# PlayerBottom.net
KiCad netlist of a schematic drawn in EAGLE
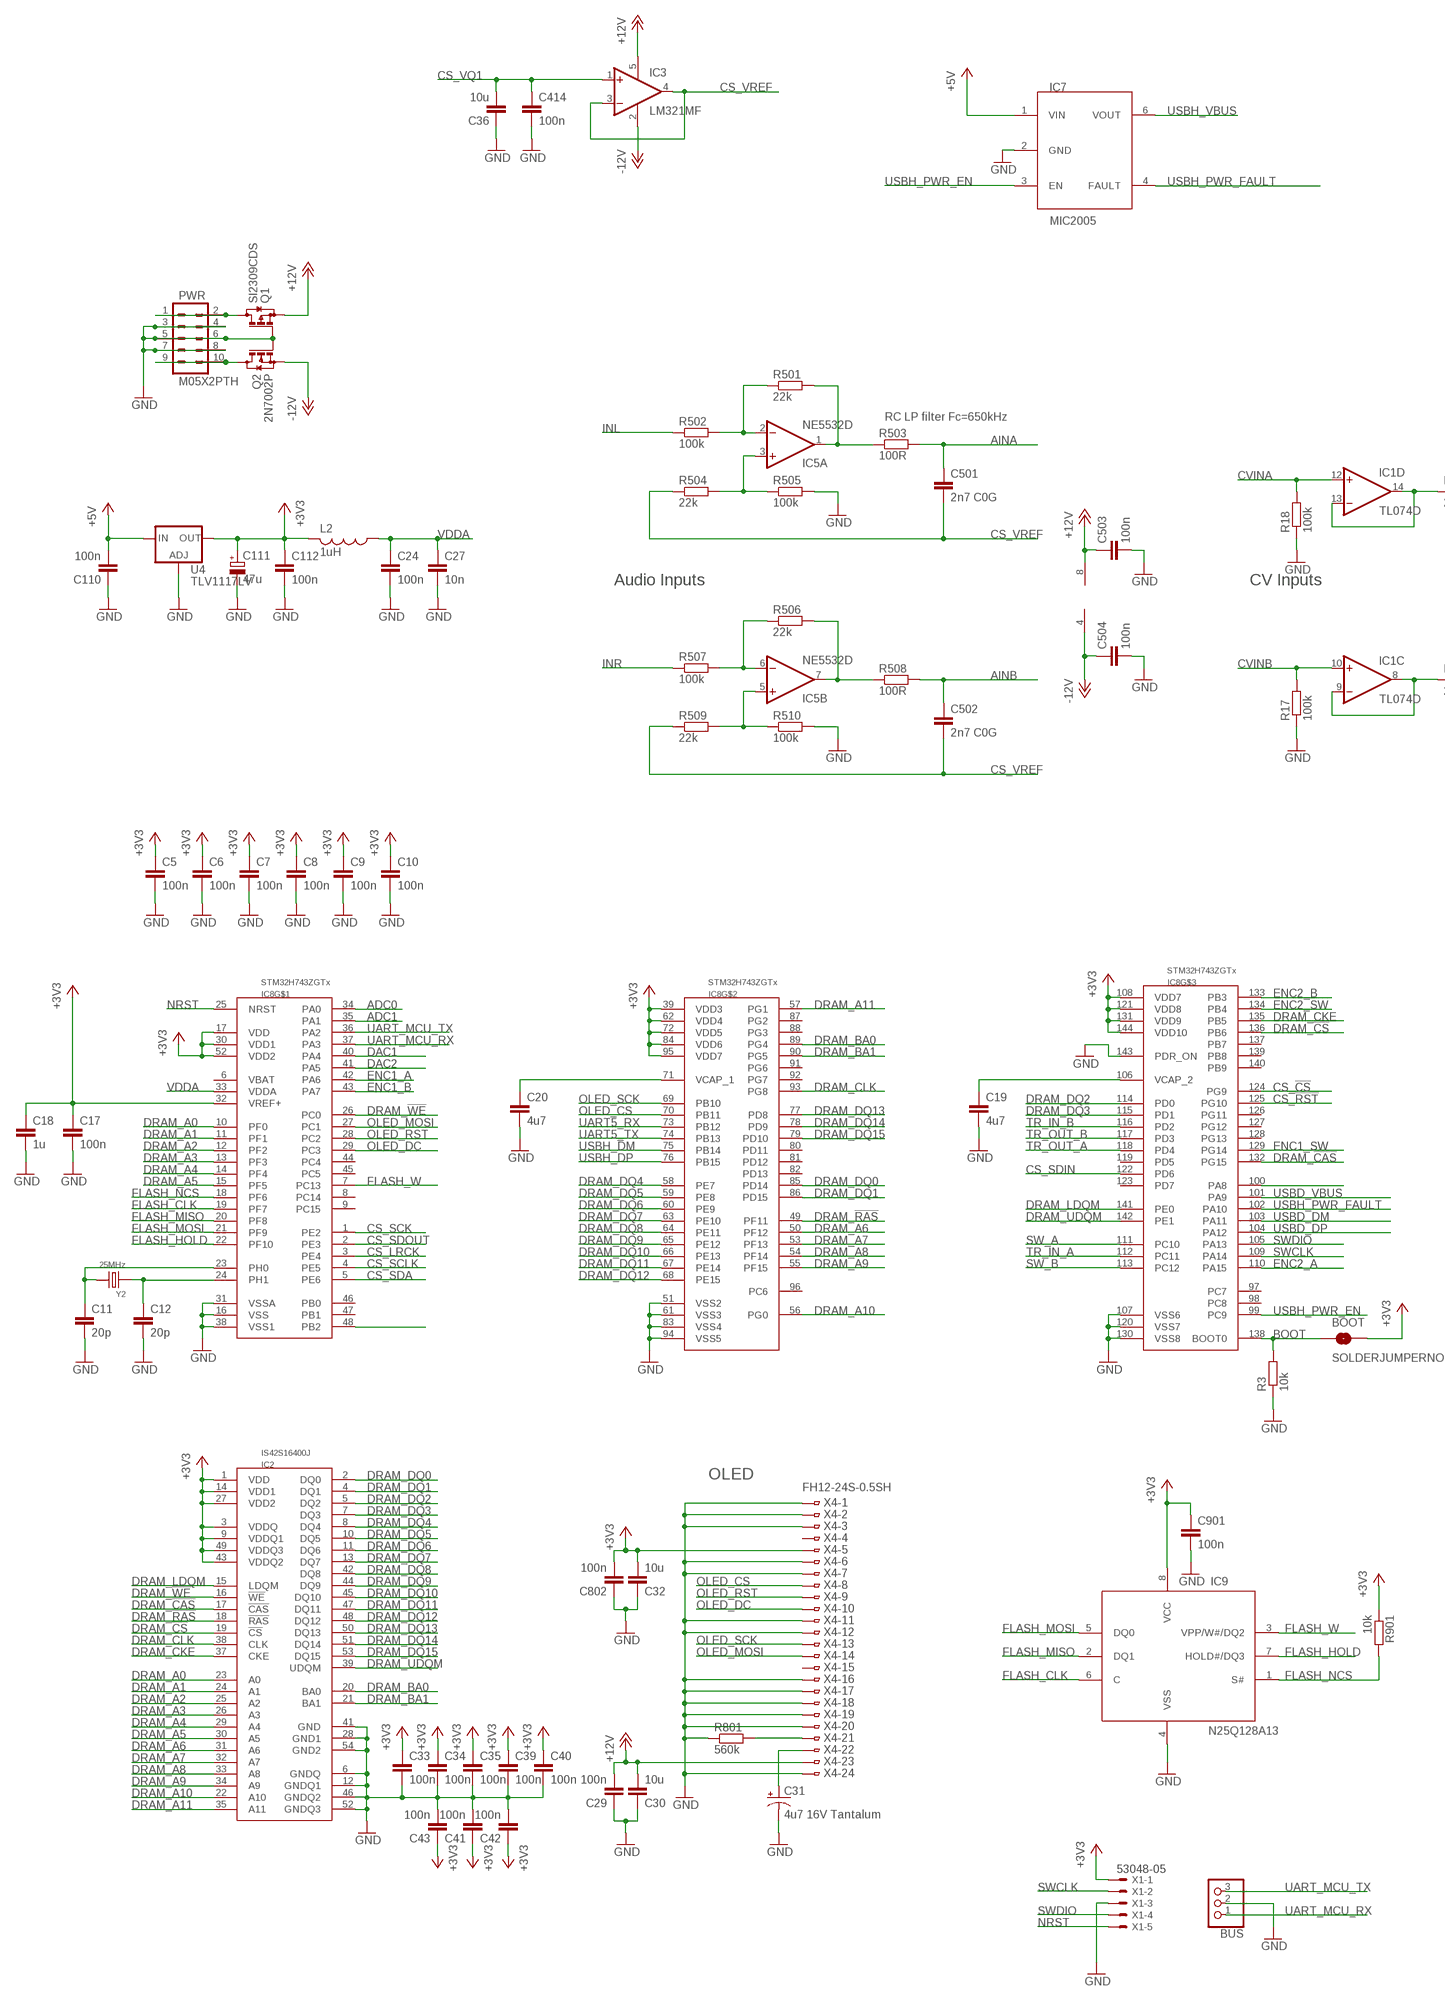
[diagram p0: schematic, sheet 1, part 1 of 2]
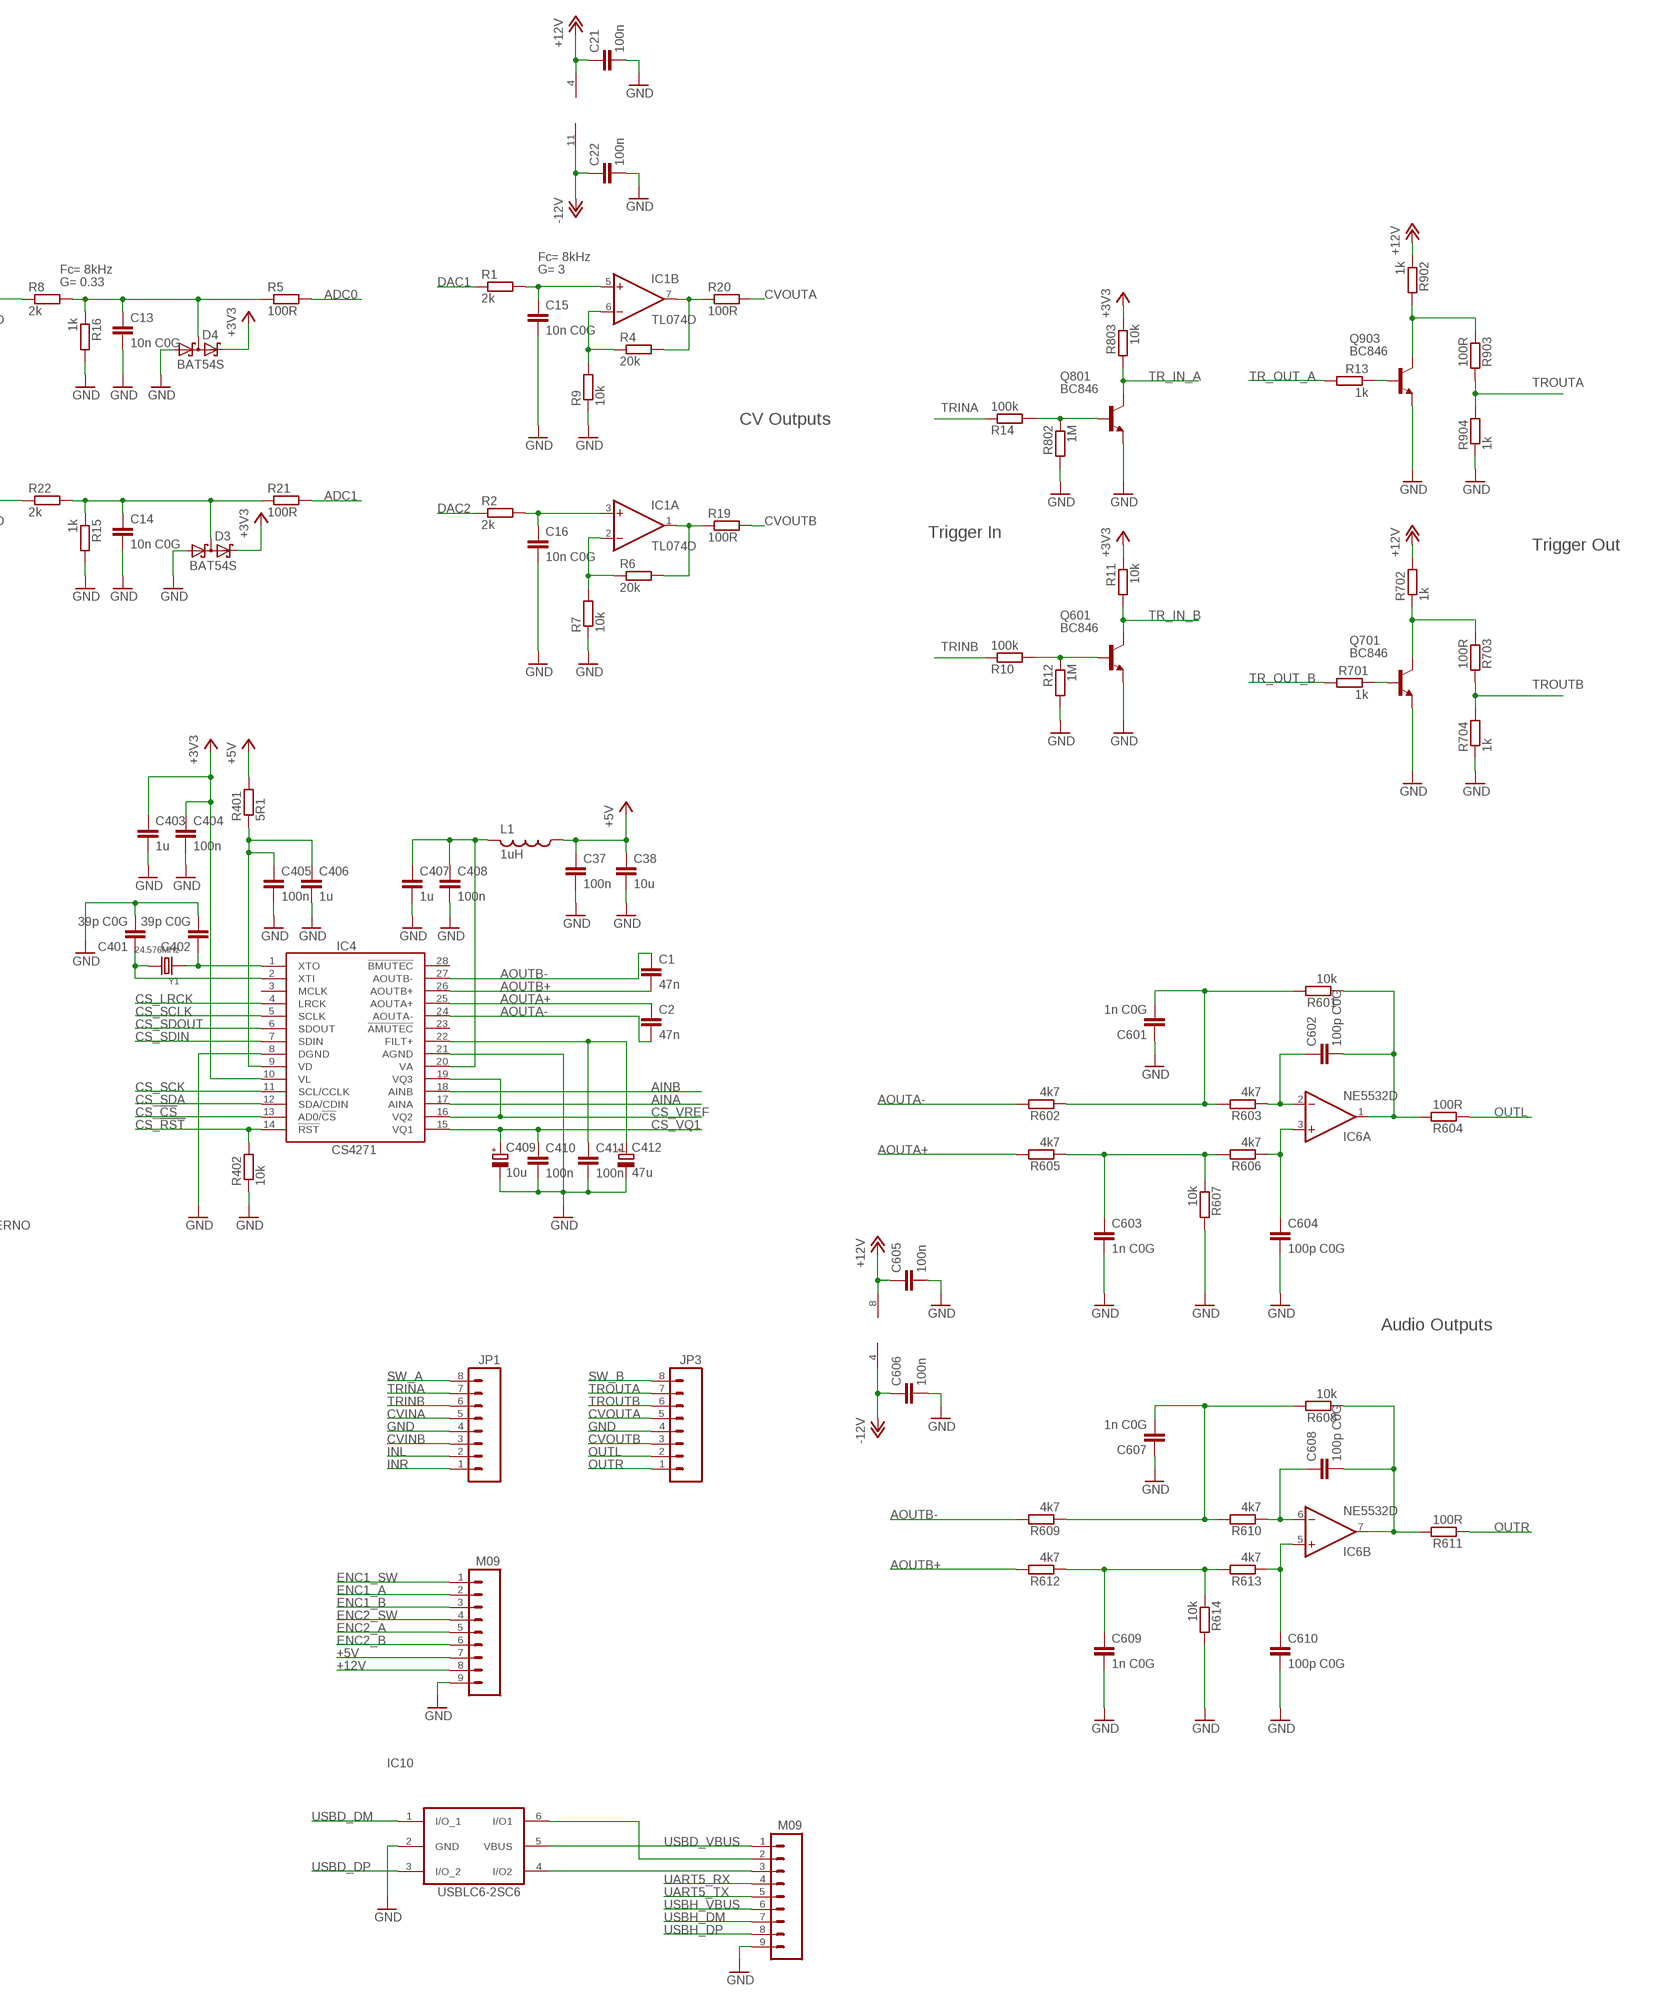
[diagram p1: schematic, sheet 1, part 2 of 2]

(export (version "E")
  (design (tool "Eeschema 10.0.6"))
  (components
    (comp (ref "BOOT")
      (value "SOLDERJUMPERNO")
      (footprint "eagle-import:SJ_2S-NO")
      (libsource (lib "eagle-import") (part "SOLDERJUMPERNO"))
    )
    (comp (ref "BUS")
      (value "CON-JST-1X03PH-TH")
      (footprint "eagle-import:JST-B3B-PH-KL")
      (libsource (lib "eagle-import") (part "CON-JST-1X03PH-TH"))
    )
    (comp (ref "C1")
      (value "47n")
      (footprint "eagle-import:C0603")
      (libsource (lib "eagle-import") (part "C-EUC0603"))
    )
    (comp (ref "C2")
      (value "47n")
      (footprint "eagle-import:C0603")
      (libsource (lib "eagle-import") (part "C-EUC0603"))
    )
    (comp (ref "C5")
      (value "100n")
      (footprint "eagle-import:C0603")
      (libsource (lib "eagle-import") (part "C-EUC0603"))
    )
    (comp (ref "C6")
      (value "100n")
      (footprint "eagle-import:C0603")
      (libsource (lib "eagle-import") (part "C-EUC0603"))
    )
    (comp (ref "C7")
      (value "100n")
      (footprint "eagle-import:C0603")
      (libsource (lib "eagle-import") (part "C-EUC0603"))
    )
    (comp (ref "C8")
      (value "100n")
      (footprint "eagle-import:C0603")
      (libsource (lib "eagle-import") (part "C-EUC0603"))
    )
    (comp (ref "C9")
      (value "100n")
      (footprint "eagle-import:C0603")
      (libsource (lib "eagle-import") (part "C-EUC0603"))
    )
    (comp (ref "C10")
      (value "100n")
      (footprint "eagle-import:C0603")
      (libsource (lib "eagle-import") (part "C-EUC0603"))
    )
    (comp (ref "C11")
      (value "20p")
      (footprint "eagle-import:C0603")
      (libsource (lib "eagle-import") (part "C-EUC0603"))
    )
    (comp (ref "C12")
      (value "20p")
      (footprint "eagle-import:C0603")
      (libsource (lib "eagle-import") (part "C-EUC0603"))
    )
    (comp (ref "C13")
      (value "10n C0G")
      (footprint "eagle-import:C0603")
      (libsource (lib "eagle-import") (part "C-EUC0603"))
    )
    (comp (ref "C14")
      (value "10n C0G")
      (footprint "eagle-import:C0603")
      (libsource (lib "eagle-import") (part "C-EUC0603"))
    )
    (comp (ref "C15")
      (value "10n C0G")
      (footprint "eagle-import:C0603")
      (libsource (lib "eagle-import") (part "C-EUC0603"))
    )
    (comp (ref "C16")
      (value "10n C0G")
      (footprint "eagle-import:C0603")
      (libsource (lib "eagle-import") (part "C-EUC0603"))
    )
    (comp (ref "C17")
      (value "100n")
      (footprint "eagle-import:C0603")
      (libsource (lib "eagle-import") (part "C-EUC0603"))
    )
    (comp (ref "C18")
      (value "1u")
      (footprint "eagle-import:C0603")
      (libsource (lib "eagle-import") (part "C-EUC0603"))
    )
    (comp (ref "C19")
      (value "4u7")
      (footprint "eagle-import:C0603")
      (libsource (lib "eagle-import") (part "C-EUC0603"))
    )
    (comp (ref "C20")
      (value "4u7")
      (footprint "eagle-import:C0603")
      (libsource (lib "eagle-import") (part "C-EUC0603"))
    )
    (comp (ref "C21")
      (value "100n")
      (footprint "eagle-import:C0603")
      (libsource (lib "eagle-import") (part "C-EUC0603"))
    )
    (comp (ref "C22")
      (value "100n")
      (footprint "eagle-import:C0603")
      (libsource (lib "eagle-import") (part "C-EUC0603"))
    )
    (comp (ref "C24")
      (value "100n")
      (footprint "eagle-import:C0603")
      (libsource (lib "eagle-import") (part "C-EUC0603"))
    )
    (comp (ref "C27")
      (value "10n")
      (footprint "eagle-import:C0603")
      (libsource (lib "eagle-import") (part "C-EUC0603"))
    )
    (comp (ref "C29")
      (value "100n")
      (footprint "eagle-import:C0603")
      (libsource (lib "eagle-import") (part "C-EUC0603"))
    )
    (comp (ref "C30")
      (value "10u")
      (footprint "eagle-import:C1206")
      (libsource (lib "eagle-import") (part "C-EUC1206"))
    )
    (comp (ref "C31")
      (value "4u7 16V Tantalum")
      (footprint "eagle-import:EIA3216")
      (libsource (lib "eagle-import") (part "CAP_POL1206"))
    )
    (comp (ref "C32")
      (value "10u")
      (footprint "eagle-import:C1206")
      (libsource (lib "eagle-import") (part "C-EUC1206"))
    )
    (comp (ref "C33")
      (value "100n")
      (footprint "eagle-import:C0603")
      (libsource (lib "eagle-import") (part "C-EUC0603"))
    )
    (comp (ref "C34")
      (value "100n")
      (footprint "eagle-import:C0603")
      (libsource (lib "eagle-import") (part "C-EUC0603"))
    )
    (comp (ref "C35")
      (value "100n")
      (footprint "eagle-import:C0603")
      (libsource (lib "eagle-import") (part "C-EUC0603"))
    )
    (comp (ref "C36")
      (value "10u")
      (footprint "eagle-import:C1206")
      (libsource (lib "eagle-import") (part "C-EUC1206"))
    )
    (comp (ref "C37")
      (value "100n")
      (footprint "eagle-import:C0603")
      (libsource (lib "eagle-import") (part "C-EUC0603"))
    )
    (comp (ref "C38")
      (value "10u")
      (footprint "eagle-import:C1206")
      (libsource (lib "eagle-import") (part "C-EUC1206"))
    )
    (comp (ref "C39")
      (value "100n")
      (footprint "eagle-import:C0603")
      (libsource (lib "eagle-import") (part "C-EUC0603"))
    )
    (comp (ref "C40")
      (value "100n")
      (footprint "eagle-import:C0603")
      (libsource (lib "eagle-import") (part "C-EUC0603"))
    )
    (comp (ref "C41")
      (value "100n")
      (footprint "eagle-import:C0603")
      (libsource (lib "eagle-import") (part "C-EUC0603"))
    )
    (comp (ref "C42")
      (value "100n")
      (footprint "eagle-import:C0603")
      (libsource (lib "eagle-import") (part "C-EUC0603"))
    )
    (comp (ref "C43")
      (value "100n")
      (footprint "eagle-import:C0603")
      (libsource (lib "eagle-import") (part "C-EUC0603"))
    )
    (comp (ref "C110")
      (value "100n")
      (footprint "eagle-import:C0603")
      (libsource (lib "eagle-import") (part "C-EUC0603"))
    )
    (comp (ref "C111")
      (value "47u")
      (footprint "eagle-import:CPOL-5")
      (libsource (lib "eagle-import") (part "CPOL-EU153CLV-0505"))
    )
    (comp (ref "C112")
      (value "100n")
      (footprint "eagle-import:C0603")
      (libsource (lib "eagle-import") (part "C-EUC0603"))
    )
    (comp (ref "C401")
      (value "39p C0G")
      (footprint "eagle-import:C0603")
      (libsource (lib "eagle-import") (part "C-EUC0603"))
    )
    (comp (ref "C402")
      (value "39p C0G")
      (footprint "eagle-import:C0603")
      (libsource (lib "eagle-import") (part "C-EUC0603"))
    )
    (comp (ref "C403")
      (value "1u")
      (footprint "eagle-import:C0603")
      (libsource (lib "eagle-import") (part "C-EUC0603"))
    )
    (comp (ref "C404")
      (value "100n")
      (footprint "eagle-import:C0603")
      (libsource (lib "eagle-import") (part "C-EUC0603"))
    )
    (comp (ref "C405")
      (value "100n")
      (footprint "eagle-import:C0603")
      (libsource (lib "eagle-import") (part "C-EUC0603"))
    )
    (comp (ref "C406")
      (value "1u")
      (footprint "eagle-import:C0603")
      (libsource (lib "eagle-import") (part "C-EUC0603"))
    )
    (comp (ref "C407")
      (value "1u")
      (footprint "eagle-import:C0603")
      (libsource (lib "eagle-import") (part "C-EUC0603"))
    )
    (comp (ref "C408")
      (value "100n")
      (footprint "eagle-import:C0603")
      (libsource (lib "eagle-import") (part "C-EUC0603"))
    )
    (comp (ref "C409")
      (value "10u")
      (footprint "eagle-import:CPOL-5")
      (libsource (lib "eagle-import") (part "CPOL-EU153CLV-0505"))
    )
    (comp (ref "C410")
      (value "100n")
      (footprint "eagle-import:C0603")
      (libsource (lib "eagle-import") (part "C-EUC0603"))
    )
    (comp (ref "C411")
      (value "100n")
      (footprint "eagle-import:C0603")
      (libsource (lib "eagle-import") (part "C-EUC0603"))
    )
    (comp (ref "C412")
      (value "47u")
      (footprint "eagle-import:CPOL-5")
      (libsource (lib "eagle-import") (part "CPOL-EU153CLV-0505"))
    )
    (comp (ref "C414")
      (value "100n")
      (footprint "eagle-import:C0603")
      (libsource (lib "eagle-import") (part "C-EUC0603"))
    )
    (comp (ref "C501")
      (value "2n7 C0G")
      (footprint "eagle-import:C0603")
      (libsource (lib "eagle-import") (part "C-EUC0603"))
    )
    (comp (ref "C502")
      (value "2n7 C0G")
      (footprint "eagle-import:C0603")
      (libsource (lib "eagle-import") (part "C-EUC0603"))
    )
    (comp (ref "C503")
      (value "100n")
      (footprint "eagle-import:C0603")
      (libsource (lib "eagle-import") (part "C-EUC0603"))
    )
    (comp (ref "C504")
      (value "100n")
      (footprint "eagle-import:C0603")
      (libsource (lib "eagle-import") (part "C-EUC0603"))
    )
    (comp (ref "C601")
      (value "1n C0G")
      (footprint "eagle-import:C0603")
      (libsource (lib "eagle-import") (part "C-EUC0603"))
    )
    (comp (ref "C602")
      (value "100p C0G")
      (footprint "eagle-import:C0603")
      (libsource (lib "eagle-import") (part "C-EUC0603"))
    )
    (comp (ref "C603")
      (value "1n C0G")
      (footprint "eagle-import:C0603")
      (libsource (lib "eagle-import") (part "C-EUC0603"))
    )
    (comp (ref "C604")
      (value "100p C0G")
      (footprint "eagle-import:C0603")
      (libsource (lib "eagle-import") (part "C-EUC0603"))
    )
    (comp (ref "C605")
      (value "100n")
      (footprint "eagle-import:C0603")
      (libsource (lib "eagle-import") (part "C-EUC0603"))
    )
    (comp (ref "C606")
      (value "100n")
      (footprint "eagle-import:C0603")
      (libsource (lib "eagle-import") (part "C-EUC0603"))
    )
    (comp (ref "C607")
      (value "1n C0G")
      (footprint "eagle-import:C0603")
      (libsource (lib "eagle-import") (part "C-EUC0603"))
    )
    (comp (ref "C608")
      (value "100p C0G")
      (footprint "eagle-import:C0603")
      (libsource (lib "eagle-import") (part "C-EUC0603"))
    )
    (comp (ref "C609")
      (value "1n C0G")
      (footprint "eagle-import:C0603")
      (libsource (lib "eagle-import") (part "C-EUC0603"))
    )
    (comp (ref "C610")
      (value "100p C0G")
      (footprint "eagle-import:C0603")
      (libsource (lib "eagle-import") (part "C-EUC0603"))
    )
    (comp (ref "C802")
      (value "100n")
      (footprint "eagle-import:C0603")
      (libsource (lib "eagle-import") (part "C-EUC0603"))
    )
    (comp (ref "C901")
      (value "100n")
      (footprint "eagle-import:C0603")
      (libsource (lib "eagle-import") (part "C-EUC0603"))
    )
    (comp (ref "D3")
      (value "BAT54S")
      (footprint "eagle-import:SOT23")
      (libsource (lib "eagle-import") (part "BAT54S"))
    )
    (comp (ref "D4")
      (value "BAT54S")
      (footprint "eagle-import:SOT23")
      (libsource (lib "eagle-import") (part "BAT54S"))
    )
    (comp (ref "IC1")
      (value "TL074D")
      (footprint "eagle-import:SO14")
      (libsource (lib "eagle-import") (part "TL074D"))
    )
    (comp (ref "IC2")
      (value "IS42S16400J")
      (footprint "eagle-import:TSOP54-400")
      (libsource (lib "eagle-import") (part "IS42S16400J"))
    )
    (comp (ref "IC3")
      (value "LM321MF")
      (footprint "eagle-import:SOT23-5")
      (libsource (lib "eagle-import") (part "LM321?MF"))
    )
    (comp (ref "IC4")
      (value "CS4271")
      (footprint "eagle-import:TSSOP28-0.65-9.7X4.4MM")
      (libsource (lib "eagle-import") (part "CS4271"))
    )
    (comp (ref "IC5")
      (value "NE5532D")
      (footprint "eagle-import:SO08")
      (libsource (lib "eagle-import") (part "NE5532D"))
    )
    (comp (ref "IC6")
      (value "NE5532D")
      (footprint "eagle-import:SO08")
      (libsource (lib "eagle-import") (part "NE5532D"))
    )
    (comp (ref "IC7")
      (value "MIC2005")
      (footprint "eagle-import:SOT23-6")
      (libsource (lib "eagle-import") (part "MIC2005"))
    )
    (comp (ref "IC8")
      (value "STM32H743ZGTx")
      (footprint "eagle-import:QFP50P2200X2200X160-144N")
      (fields (field (name "OC_FARNELL") "2484975"))
      (libsource (lib "eagle-import") (part "STM32F42XZ/43XZ(144PIN)LQFP144"))
    )
    (comp (ref "IC9")
      (value "N25Q128A13")
      (footprint "eagle-import:SO8W")
      (libsource (lib "eagle-import") (part "N25Q128A13"))
    )
    (comp (ref "IC10")
      (value "USBLC6-2SC6")
      (footprint "eagle-import:SOT-23-6L")
      (libsource (lib "eagle-import") (part "USBLC6-2SC6"))
    )
    (comp (ref "JP1")
      (value "M081X08")
      (footprint "eagle-import:1X08")
      (libsource (lib "eagle-import") (part "M081X08"))
    )
    (comp (ref "JP2")
      (value "M09")
      (footprint "eagle-import:1X09")
      (libsource (lib "eagle-import") (part "M09"))
    )
    (comp (ref "JP3")
      (value "M081X08")
      (footprint "eagle-import:1X08")
      (libsource (lib "eagle-import") (part "M081X08"))
    )
    (comp (ref "JP4")
      (value "M09")
      (footprint "eagle-import:1X09")
      (libsource (lib "eagle-import") (part "M09"))
    )
    (comp (ref "L1")
      (value "1uH")
      (footprint "eagle-import:0603")
      (libsource (lib "eagle-import") (part "INDUCTOR"))
    )
    (comp (ref "L2")
      (value "1uH")
      (footprint "eagle-import:0603")
      (libsource (lib "eagle-import") (part "INDUCTOR"))
    )
    (comp (ref "PWR")
      (value "M05X2PTH")
      (footprint "eagle-import:AVR_ICSP")
      (libsource (lib "eagle-import") (part "M05X2PTH"))
    )
    (comp (ref "Q1")
      (value "SI2309CDS")
      (footprint "eagle-import:SOT23")
      (libsource (lib "eagle-import") (part "BSS84"))
    )
    (comp (ref "Q2")
      (value "2N7002P")
      (footprint "eagle-import:SOT23")
      (libsource (lib "eagle-import") (part "BSS123"))
    )
    (comp (ref "Q601")
      (value "BC846")
      (footprint "eagle-import:SOT23")
      (libsource (lib "eagle-import") (part "BC846"))
    )
    (comp (ref "Q701")
      (value "BC846")
      (footprint "eagle-import:SOT23")
      (libsource (lib "eagle-import") (part "BC846"))
    )
    (comp (ref "Q801")
      (value "BC846")
      (footprint "eagle-import:SOT23")
      (libsource (lib "eagle-import") (part "BC846"))
    )
    (comp (ref "Q903")
      (value "BC846")
      (footprint "eagle-import:SOT23")
      (libsource (lib "eagle-import") (part "BC846"))
    )
    (comp (ref "R1")
      (value "2k")
      (footprint "eagle-import:0603")
      (libsource (lib "eagle-import") (part "R-EU_0603"))
    )
    (comp (ref "R2")
      (value "2k")
      (footprint "eagle-import:0603")
      (libsource (lib "eagle-import") (part "R-EU_0603"))
    )
    (comp (ref "R3")
      (value "10k")
      (footprint "eagle-import:0603")
      (libsource (lib "eagle-import") (part "R-EU_0603"))
    )
    (comp (ref "R4")
      (value "20k")
      (footprint "eagle-import:0603")
      (libsource (lib "eagle-import") (part "R-EU_0603"))
    )
    (comp (ref "R5")
      (value "100R")
      (footprint "eagle-import:0603")
      (libsource (lib "eagle-import") (part "R-EU_0603"))
    )
    (comp (ref "R6")
      (value "20k")
      (footprint "eagle-import:0603")
      (libsource (lib "eagle-import") (part "R-EU_0603"))
    )
    (comp (ref "R7")
      (value "10k")
      (footprint "eagle-import:0603")
      (libsource (lib "eagle-import") (part "R-EU_0603"))
    )
    (comp (ref "R8")
      (value "2k")
      (footprint "eagle-import:0603")
      (libsource (lib "eagle-import") (part "R-EU_0603"))
    )
    (comp (ref "R9")
      (value "10k")
      (footprint "eagle-import:0603")
      (libsource (lib "eagle-import") (part "R-EU_0603"))
    )
    (comp (ref "R10")
      (value "100k")
      (footprint "eagle-import:0603")
      (libsource (lib "eagle-import") (part "R-EU_0603"))
    )
    (comp (ref "R11")
      (value "10k")
      (footprint "eagle-import:0603")
      (libsource (lib "eagle-import") (part "R-EU_0603"))
    )
    (comp (ref "R12")
      (value "1M")
      (footprint "eagle-import:0603")
      (libsource (lib "eagle-import") (part "R-EU_0603"))
    )
    (comp (ref "R13")
      (value "1k")
      (footprint "eagle-import:0603")
      (libsource (lib "eagle-import") (part "R-EU_0603"))
    )
    (comp (ref "R14")
      (value "100k")
      (footprint "eagle-import:0603")
      (libsource (lib "eagle-import") (part "R-EU_0603"))
    )
    (comp (ref "R15")
      (value "1k")
      (footprint "eagle-import:0603")
      (libsource (lib "eagle-import") (part "R-EU_0603"))
    )
    (comp (ref "R16")
      (value "1k")
      (footprint "eagle-import:0603")
      (libsource (lib "eagle-import") (part "R-EU_0603"))
    )
    (comp (ref "R17")
      (value "100k")
      (footprint "eagle-import:0603")
      (libsource (lib "eagle-import") (part "R-EU_0603"))
    )
    (comp (ref "R18")
      (value "100k")
      (footprint "eagle-import:0603")
      (libsource (lib "eagle-import") (part "R-EU_0603"))
    )
    (comp (ref "R19")
      (value "100R")
      (footprint "eagle-import:0603")
      (libsource (lib "eagle-import") (part "R-EU_0603"))
    )
    (comp (ref "R20")
      (value "100R")
      (footprint "eagle-import:0603")
      (libsource (lib "eagle-import") (part "R-EU_0603"))
    )
    (comp (ref "R21")
      (value "100R")
      (footprint "eagle-import:0603")
      (libsource (lib "eagle-import") (part "R-EU_0603"))
    )
    (comp (ref "R22")
      (value "2k")
      (footprint "eagle-import:0603")
      (libsource (lib "eagle-import") (part "R-EU_0603"))
    )
    (comp (ref "R401")
      (value "5R1")
      (footprint "eagle-import:0603")
      (libsource (lib "eagle-import") (part "R-EU_0603"))
    )
    (comp (ref "R402")
      (value "10k")
      (footprint "eagle-import:0603")
      (libsource (lib "eagle-import") (part "R-EU_0603"))
    )
    (comp (ref "R501")
      (value "22k")
      (footprint "eagle-import:0603")
      (libsource (lib "eagle-import") (part "R-EU_0603"))
    )
    (comp (ref "R502")
      (value "100k")
      (footprint "eagle-import:0603")
      (libsource (lib "eagle-import") (part "R-EU_0603"))
    )
    (comp (ref "R503")
      (value "100R")
      (footprint "eagle-import:0603")
      (libsource (lib "eagle-import") (part "R-EU_0603"))
    )
    (comp (ref "R504")
      (value "22k")
      (footprint "eagle-import:0603")
      (libsource (lib "eagle-import") (part "R-EU_0603"))
    )
    (comp (ref "R505")
      (value "100k")
      (footprint "eagle-import:0603")
      (libsource (lib "eagle-import") (part "R-EU_0603"))
    )
    (comp (ref "R506")
      (value "22k")
      (footprint "eagle-import:0603")
      (libsource (lib "eagle-import") (part "R-EU_0603"))
    )
    (comp (ref "R507")
      (value "100k")
      (footprint "eagle-import:0603")
      (libsource (lib "eagle-import") (part "R-EU_0603"))
    )
    (comp (ref "R508")
      (value "100R")
      (footprint "eagle-import:0603")
      (libsource (lib "eagle-import") (part "R-EU_0603"))
    )
    (comp (ref "R509")
      (value "22k")
      (footprint "eagle-import:0603")
      (libsource (lib "eagle-import") (part "R-EU_0603"))
    )
    (comp (ref "R510")
      (value "100k")
      (footprint "eagle-import:0603")
      (libsource (lib "eagle-import") (part "R-EU_0603"))
    )
    (comp (ref "R601")
      (value "10k")
      (footprint "eagle-import:0603")
      (libsource (lib "eagle-import") (part "R-EU_0603"))
    )
    (comp (ref "R602")
      (value "4k7")
      (footprint "eagle-import:0603")
      (libsource (lib "eagle-import") (part "R-EU_0603"))
    )
    (comp (ref "R603")
      (value "4k7")
      (footprint "eagle-import:0603")
      (libsource (lib "eagle-import") (part "R-EU_0603"))
    )
    (comp (ref "R604")
      (value "100R")
      (footprint "eagle-import:0603")
      (libsource (lib "eagle-import") (part "R-EU_0603"))
    )
    (comp (ref "R605")
      (value "4k7")
      (footprint "eagle-import:0603")
      (libsource (lib "eagle-import") (part "R-EU_0603"))
    )
    (comp (ref "R606")
      (value "4k7")
      (footprint "eagle-import:0603")
      (libsource (lib "eagle-import") (part "R-EU_0603"))
    )
    (comp (ref "R607")
      (value "10k")
      (footprint "eagle-import:0603")
      (libsource (lib "eagle-import") (part "R-EU_0603"))
    )
    (comp (ref "R608")
      (value "10k")
      (footprint "eagle-import:0603")
      (libsource (lib "eagle-import") (part "R-EU_0603"))
    )
    (comp (ref "R609")
      (value "4k7")
      (footprint "eagle-import:0603")
      (libsource (lib "eagle-import") (part "R-EU_0603"))
    )
    (comp (ref "R610")
      (value "4k7")
      (footprint "eagle-import:0603")
      (libsource (lib "eagle-import") (part "R-EU_0603"))
    )
    (comp (ref "R611")
      (value "100R")
      (footprint "eagle-import:0603")
      (libsource (lib "eagle-import") (part "R-EU_0603"))
    )
    (comp (ref "R612")
      (value "4k7")
      (footprint "eagle-import:0603")
      (libsource (lib "eagle-import") (part "R-EU_0603"))
    )
    (comp (ref "R613")
      (value "4k7")
      (footprint "eagle-import:0603")
      (libsource (lib "eagle-import") (part "R-EU_0603"))
    )
    (comp (ref "R614")
      (value "10k")
      (footprint "eagle-import:0603")
      (libsource (lib "eagle-import") (part "R-EU_0603"))
    )
    (comp (ref "R701")
      (value "1k")
      (footprint "eagle-import:0603")
      (libsource (lib "eagle-import") (part "R-EU_0603"))
    )
    (comp (ref "R702")
      (value "1k")
      (footprint "eagle-import:0603")
      (libsource (lib "eagle-import") (part "R-EU_0603"))
    )
    (comp (ref "R703")
      (value "100R")
      (footprint "eagle-import:0603")
      (libsource (lib "eagle-import") (part "R-EU_0603"))
    )
    (comp (ref "R704")
      (value "1k")
      (footprint "eagle-import:0603")
      (libsource (lib "eagle-import") (part "R-EU_0603"))
    )
    (comp (ref "R801")
      (value "560k")
      (footprint "eagle-import:0603")
      (libsource (lib "eagle-import") (part "R-EU_0603"))
    )
    (comp (ref "R802")
      (value "1M")
      (footprint "eagle-import:0603")
      (libsource (lib "eagle-import") (part "R-EU_0603"))
    )
    (comp (ref "R803")
      (value "10k")
      (footprint "eagle-import:0603")
      (libsource (lib "eagle-import") (part "R-EU_0603"))
    )
    (comp (ref "R901")
      (value "10k")
      (footprint "eagle-import:0603")
      (libsource (lib "eagle-import") (part "R-EU_0603"))
    )
    (comp (ref "R902")
      (value "1k")
      (footprint "eagle-import:0603")
      (libsource (lib "eagle-import") (part "R-EU_0603"))
    )
    (comp (ref "R903")
      (value "100R")
      (footprint "eagle-import:0603")
      (libsource (lib "eagle-import") (part "R-EU_0603"))
    )
    (comp (ref "R904")
      (value "1k")
      (footprint "eagle-import:0603")
      (libsource (lib "eagle-import") (part "R-EU_0603"))
    )
    (comp (ref "U4")
      (value "TLV1117LV")
      (footprint "eagle-import:SOT223")
      (libsource (lib "eagle-import") (part "LD117A?S33TR"))
    )
    (comp (ref "X1")
      (value "53048-05")
      (footprint "eagle-import:53048-05")
      (fields (field (name "MF") "MOLEX") (field (name "MPN") "53048-0510"))
      (libsource (lib "eagle-import") (part "53?-05048"))
    )
    (comp (ref "X4")
      (value "FH12-24S-0.5SH")
      (footprint "eagle-import:FH12-24S-0.5SH")
      (fields (field (name "MPN") "FH12-24S-0.5SH(55)"))
      (libsource (lib "eagle-import") (part "FH12-24S-0.5SH"))
    )
    (comp (ref "Y1")
      (value "24.576MHz")
      (footprint "eagle-import:X2-SMD-5.0X3.2X1.3MM")
      (fields (field (name "MPN") "5032/2P"))
      (libsource (lib "eagle-import") (part "SMD-CRYSTAL-8MHZ-20PF-20PPM(2P-5.0X3.2MM)"))
    )
    (comp (ref "Y2")
      (value "25MHz")
      (footprint "eagle-import:X2-SMD-5.0X3.2X1.3MM")
      (fields (field (name "MPN") "5032/2P"))
      (libsource (lib "eagle-import") (part "SMD-CRYSTAL-8MHZ-20PF-20PPM(2P-5.0X3.2MM)"))
    )
  )
  (nets
    (net (code "1") (name "+3V3") (class "Default")
      (node (ref "BOOT") (pin "2") (pinfunction "2_2") (pintype "passive"))
      (node (ref "C10") (pin "1") (pinfunction "1_1") (pintype "passive"))
      (node (ref "C111") (pin "+") (pinfunction "+_+") (pintype "passive"))
      (node (ref "C112") (pin "1") (pinfunction "1_1") (pintype "passive"))
      (node (ref "C17") (pin "1") (pinfunction "1_1") (pintype "passive"))
      (node (ref "C18") (pin "1") (pinfunction "1_1") (pintype "passive"))
      (node (ref "C32") (pin "2") (pinfunction "2_2") (pintype "passive"))
      (node (ref "C33") (pin "1") (pinfunction "1_1") (pintype "passive"))
      (node (ref "C34") (pin "1") (pinfunction "1_1") (pintype "passive"))
      (node (ref "C35") (pin "1") (pinfunction "1_1") (pintype "passive"))
      (node (ref "C39") (pin "1") (pinfunction "1_1") (pintype "passive"))
      (node (ref "C40") (pin "1") (pinfunction "1_1") (pintype "passive"))
      (node (ref "C403") (pin "1") (pinfunction "1_1") (pintype "passive"))
      (node (ref "C404") (pin "1") (pinfunction "1_1") (pintype "passive"))
      (node (ref "C41") (pin "1") (pinfunction "1_1") (pintype "passive"))
      (node (ref "C42") (pin "1") (pinfunction "1_1") (pintype "passive"))
      (node (ref "C43") (pin "1") (pinfunction "1_1") (pintype "passive"))
      (node (ref "C5") (pin "1") (pinfunction "1_1") (pintype "passive"))
      (node (ref "C6") (pin "1") (pinfunction "1_1") (pintype "passive"))
      (node (ref "C7") (pin "1") (pinfunction "1_1") (pintype "passive"))
      (node (ref "C8") (pin "1") (pinfunction "1_1") (pintype "passive"))
      (node (ref "C802") (pin "2") (pinfunction "2_2") (pintype "passive"))
      (node (ref "C9") (pin "1") (pinfunction "1_1") (pintype "passive"))
      (node (ref "C901") (pin "1") (pinfunction "1_1") (pintype "passive"))
      (node (ref "D3") (pin "2") (pinfunction "C2_2") (pintype "passive"))
      (node (ref "D4") (pin "2") (pinfunction "C2_2") (pintype "passive"))
      (node (ref "IC2") (pin "1") (pinfunction "VDD_1") (pintype "bidirectional"))
      (node (ref "IC2") (pin "14") (pinfunction "VDD1_14") (pintype "bidirectional"))
      (node (ref "IC2") (pin "27") (pinfunction "VDD2_27") (pintype "bidirectional"))
      (node (ref "IC2") (pin "3") (pinfunction "VDDQ_3") (pintype "bidirectional"))
      (node (ref "IC2") (pin "43") (pinfunction "VDDQ2_43") (pintype "bidirectional"))
      (node (ref "IC2") (pin "49") (pinfunction "VDDQ3_49") (pintype "bidirectional"))
      (node (ref "IC2") (pin "9") (pinfunction "VDDQ1_9") (pintype "bidirectional"))
      (node (ref "IC4") (pin "10") (pinfunction "VL_10") (pintype "bidirectional"))
      (node (ref "IC8") (pin "108") (pinfunction "VDD7_108") (pintype "bidirectional"))
      (node (ref "IC8") (pin "121") (pinfunction "VDD8_121") (pintype "bidirectional"))
      (node (ref "IC8") (pin "131") (pinfunction "VDD9_131") (pintype "bidirectional"))
      (node (ref "IC8") (pin "144") (pinfunction "VDD10_144") (pintype "bidirectional"))
      (node (ref "IC8") (pin "17") (pinfunction "VDD_17") (pintype "bidirectional"))
      (node (ref "IC8") (pin "30") (pinfunction "VDD1_30") (pintype "bidirectional"))
      (node (ref "IC8") (pin "32") (pinfunction "VREF+_32") (pintype "bidirectional"))
      (node (ref "IC8") (pin "39") (pinfunction "VDD3_39") (pintype "bidirectional"))
      (node (ref "IC8") (pin "52") (pinfunction "VDD2_52") (pintype "bidirectional"))
      (node (ref "IC8") (pin "62") (pinfunction "VDD4_62") (pintype "bidirectional"))
      (node (ref "IC8") (pin "72") (pinfunction "VDD5_72") (pintype "bidirectional"))
      (node (ref "IC8") (pin "84") (pinfunction "VDD6_84") (pintype "bidirectional"))
      (node (ref "IC8") (pin "95") (pinfunction "VDD7_95") (pintype "bidirectional"))
      (node (ref "IC9") (pin "8") (pinfunction "VCC_8") (pintype "bidirectional"))
      (node (ref "L2") (pin "2") (pinfunction "2_2") (pintype "passive"))
      (node (ref "R11") (pin "1") (pinfunction "1_1") (pintype "passive"))
      (node (ref "R803") (pin "1") (pinfunction "1_1") (pintype "passive"))
      (node (ref "R901") (pin "1") (pinfunction "1_1") (pintype "passive"))
      (node (ref "U4") (pin "4") (pinfunction "OUT_4") (pintype "passive"))
      (node (ref "X1") (pin "1") (pinfunction "S_1") (pintype "passive"))
      (node (ref "X4") (pin "5") (pinfunction "1_5") (pintype "passive"))
    )
    (net (code "2") (name "+5V") (class "Default")
      (node (ref "C110") (pin "2") (pinfunction "2_2") (pintype "passive"))
      (node (ref "C37") (pin "1") (pinfunction "1_1") (pintype "passive"))
      (node (ref "C38") (pin "1") (pinfunction "1_1") (pintype "passive"))
      (node (ref "IC7") (pin "1") (pinfunction "VIN_1") (pintype "power_in"))
      (node (ref "JP4") (pin "7") (pinfunction "7_7") (pintype "passive"))
      (node (ref "L1") (pin "1") (pinfunction "1_1") (pintype "passive"))
      (node (ref "R401") (pin "2") (pinfunction "2_2") (pintype "passive"))
      (node (ref "U4") (pin "3") (pinfunction "IN_3") (pintype "input"))
    )
    (net (code "3") (name "+12V") (class "Default")
      (node (ref "C21") (pin "1") (pinfunction "1_1") (pintype "passive"))
      (node (ref "C29") (pin "2") (pinfunction "2_2") (pintype "passive"))
      (node (ref "C30") (pin "2") (pinfunction "2_2") (pintype "passive"))
      (node (ref "C503") (pin "1") (pinfunction "1_1") (pintype "passive"))
      (node (ref "C605") (pin "1") (pinfunction "1_1") (pintype "passive"))
      (node (ref "IC1") (pin "4") (pinfunction "V+_4") (pintype "power_in"))
      (node (ref "IC3") (pin "5") (pinfunction "V+_5") (pintype "power_in"))
      (node (ref "IC5") (pin "8") (pinfunction "V+_8") (pintype "power_in"))
      (node (ref "IC6") (pin "8") (pinfunction "V+_8") (pintype "power_in"))
      (node (ref "JP4") (pin "8") (pinfunction "8_8") (pintype "passive"))
      (node (ref "Q1") (pin "2") (pinfunction "S_2") (pintype "passive"))
      (node (ref "R702") (pin "2") (pinfunction "2_2") (pintype "passive"))
      (node (ref "R902") (pin "1") (pinfunction "1_1") (pintype "passive"))
      (node (ref "X4") (pin "23") (pinfunction "1_23") (pintype "passive"))
    )
    (net (code "4") (name "-12V") (class "Default")
      (node (ref "C22") (pin "1") (pinfunction "1_1") (pintype "passive"))
      (node (ref "C504") (pin "1") (pinfunction "1_1") (pintype "passive"))
      (node (ref "C606") (pin "1") (pinfunction "1_1") (pintype "passive"))
      (node (ref "IC1") (pin "11") (pinfunction "V-_11") (pintype "power_in"))
      (node (ref "IC3") (pin "2") (pinfunction "V-_2") (pintype "power_in"))
      (node (ref "IC5") (pin "4") (pinfunction "V-_4") (pintype "power_in"))
      (node (ref "IC6") (pin "4") (pinfunction "V-_4") (pintype "power_in"))
      (node (ref "Q2") (pin "2") (pinfunction "S_2") (pintype "passive"))
    )
    (net (code "5") (name "/ADC0") (class "Default")
      (node (ref "IC8") (pin "34") (pinfunction "PA0_34") (pintype "bidirectional"))
      (node (ref "R5") (pin "2") (pinfunction "2_2") (pintype "passive"))
    )
    (net (code "6") (name "/ADC1") (class "Default")
      (node (ref "IC8") (pin "35") (pinfunction "PA1_35") (pintype "bidirectional"))
      (node (ref "R21") (pin "2") (pinfunction "2_2") (pintype "passive"))
    )
    (net (code "7") (name "/AINA") (class "Default")
      (node (ref "C501") (pin "1") (pinfunction "1_1") (pintype "passive"))
      (node (ref "IC4") (pin "17") (pinfunction "AINA_17") (pintype "bidirectional"))
      (node (ref "R503") (pin "2") (pinfunction "2_2") (pintype "passive"))
    )
    (net (code "8") (name "/AINB") (class "Default")
      (node (ref "C502") (pin "1") (pinfunction "1_1") (pintype "passive"))
      (node (ref "IC4") (pin "18") (pinfunction "AINB_18") (pintype "bidirectional"))
      (node (ref "R508") (pin "2") (pinfunction "2_2") (pintype "passive"))
    )
    (net (code "9") (name "/AOUTA+") (class "Default")
      (node (ref "C2") (pin "1") (pinfunction "1_1") (pintype "passive"))
      (node (ref "IC4") (pin "25") (pinfunction "AOUTA+_25") (pintype "bidirectional"))
      (node (ref "R605") (pin "2") (pinfunction "2_2") (pintype "passive"))
    )
    (net (code "10") (name "/AOUTA-") (class "Default")
      (node (ref "C2") (pin "2") (pinfunction "2_2") (pintype "passive"))
      (node (ref "IC4") (pin "24") (pinfunction "AOUTA-_24") (pintype "bidirectional"))
      (node (ref "R602") (pin "2") (pinfunction "2_2") (pintype "passive"))
    )
    (net (code "11") (name "/AOUTB+") (class "Default")
      (node (ref "C1") (pin "2") (pinfunction "2_2") (pintype "passive"))
      (node (ref "IC4") (pin "26") (pinfunction "AOUTB+_26") (pintype "bidirectional"))
      (node (ref "R612") (pin "2") (pinfunction "2_2") (pintype "passive"))
    )
    (net (code "12") (name "/AOUTB-") (class "Default")
      (node (ref "C1") (pin "1") (pinfunction "1_1") (pintype "passive"))
      (node (ref "IC4") (pin "27") (pinfunction "AOUTB-_27") (pintype "bidirectional"))
      (node (ref "R609") (pin "2") (pinfunction "2_2") (pintype "passive"))
    )
    (net (code "13") (name "/BOOT") (class "Default")
      (node (ref "BOOT") (pin "1") (pinfunction "1_1") (pintype "passive"))
      (node (ref "IC8") (pin "138") (pinfunction "BOOT0_138") (pintype "bidirectional"))
      (node (ref "R3") (pin "2") (pinfunction "2_2") (pintype "passive"))
    )
    (net (code "14") (name "/CS_LRCK") (class "Default")
      (node (ref "IC4") (pin "4") (pinfunction "LRCK_4") (pintype "bidirectional"))
      (node (ref "IC8") (pin "3") (pinfunction "PE4_3") (pintype "bidirectional"))
    )
    (net (code "15") (name "/CS_SCK") (class "Default")
      (node (ref "IC4") (pin "11") (pinfunction "SCL/CCLK_11") (pintype "bidirectional"))
      (node (ref "IC8") (pin "1") (pinfunction "PE2_1") (pintype "bidirectional"))
    )
    (net (code "16") (name "/CS_SCLK") (class "Default")
      (node (ref "IC4") (pin "5") (pinfunction "SCLK_5") (pintype "bidirectional"))
      (node (ref "IC8") (pin "4") (pinfunction "PE5_4") (pintype "bidirectional"))
    )
    (net (code "17") (name "/CS_SDA") (class "Default")
      (node (ref "IC4") (pin "12") (pinfunction "SDA/CDIN_12") (pintype "bidirectional"))
      (node (ref "IC8") (pin "5") (pinfunction "PE6_5") (pintype "bidirectional"))
    )
    (net (code "18") (name "/CS_SDIN") (class "Default")
      (node (ref "IC4") (pin "7") (pinfunction "SDIN_7") (pintype "bidirectional"))
      (node (ref "IC8") (pin "122") (pinfunction "PD6_122") (pintype "bidirectional"))
    )
    (net (code "19") (name "/CS_SDOUT") (class "Default")
      (node (ref "IC4") (pin "6") (pinfunction "SDOUT_6") (pintype "bidirectional"))
      (node (ref "IC8") (pin "2") (pinfunction "PE3_2") (pintype "bidirectional"))
    )
    (net (code "20") (name "/CS_VQ1") (class "Default")
      (node (ref "C36") (pin "2") (pinfunction "2_2") (pintype "passive"))
      (node (ref "C409") (pin "+") (pinfunction "+_+") (pintype "passive"))
      (node (ref "C410") (pin "1") (pinfunction "1_1") (pintype "passive"))
      (node (ref "C414") (pin "1") (pinfunction "1_1") (pintype "passive"))
      (node (ref "IC3") (pin "1") (pinfunction "+IN_1") (pintype "input"))
      (node (ref "IC4") (pin "15") (pinfunction "VQ1_15") (pintype "bidirectional"))
    )
    (net (code "21") (name "/CS_VREF") (class "Default")
      (node (ref "C501") (pin "2") (pinfunction "2_2") (pintype "passive"))
      (node (ref "C502") (pin "2") (pinfunction "2_2") (pintype "passive"))
      (node (ref "IC3") (pin "3") (pinfunction "-IN_3") (pintype "input"))
      (node (ref "IC3") (pin "4") (pinfunction "OUT_4") (pintype "output"))
      (node (ref "IC4") (pin "16") (pinfunction "VQ2_16") (pintype "bidirectional"))
      (node (ref "IC4") (pin "19") (pinfunction "VQ3_19") (pintype "bidirectional"))
      (node (ref "R504") (pin "1") (pinfunction "1_1") (pintype "passive"))
      (node (ref "R509") (pin "1") (pinfunction "1_1") (pintype "passive"))
    )
    (net (code "22") (name "/CS_~{CS}") (class "Default")
      (node (ref "IC4") (pin "13") (pinfunction "AD0/~{CS}_13") (pintype "bidirectional"))
      (node (ref "IC8") (pin "124") (pinfunction "PG9_124") (pintype "bidirectional"))
    )
    (net (code "23") (name "/CS_~{RST}") (class "Default")
      (node (ref "IC4") (pin "14") (pinfunction "~{RST}_14") (pintype "bidirectional"))
      (node (ref "IC8") (pin "125") (pinfunction "PG10_125") (pintype "bidirectional"))
      (node (ref "R402") (pin "2") (pinfunction "2_2") (pintype "passive"))
    )
    (net (code "24") (name "/CVINA") (class "Default")
      (node (ref "IC1") (pin "12") (pinfunction "+IN_12") (pintype "input"))
      (node (ref "JP1") (pin "5") (pinfunction "5_5") (pintype "passive"))
      (node (ref "R18") (pin "2") (pinfunction "2_2") (pintype "passive"))
    )
    (net (code "25") (name "/CVINB") (class "Default")
      (node (ref "IC1") (pin "10") (pinfunction "+IN_10") (pintype "input"))
      (node (ref "JP1") (pin "3") (pinfunction "3_3") (pintype "passive"))
      (node (ref "R17") (pin "2") (pinfunction "2_2") (pintype "passive"))
    )
    (net (code "26") (name "/CVOUTA") (class "Default")
      (node (ref "JP3") (pin "5") (pinfunction "5_5") (pintype "passive"))
      (node (ref "R20") (pin "2") (pinfunction "2_2") (pintype "passive"))
    )
    (net (code "27") (name "/CVOUTB") (class "Default")
      (node (ref "JP3") (pin "3") (pinfunction "3_3") (pintype "passive"))
      (node (ref "R19") (pin "2") (pinfunction "2_2") (pintype "passive"))
    )
    (net (code "28") (name "/DAC1") (class "Default")
      (node (ref "IC8") (pin "40") (pinfunction "PA4_40") (pintype "bidirectional"))
      (node (ref "R1") (pin "1") (pinfunction "1_1") (pintype "passive"))
    )
    (net (code "29") (name "/DAC2") (class "Default")
      (node (ref "IC8") (pin "41") (pinfunction "PA5_41") (pintype "bidirectional"))
      (node (ref "R2") (pin "1") (pinfunction "1_1") (pintype "passive"))
    )
    (net (code "30") (name "/DRAM_A0") (class "Default")
      (node (ref "IC2") (pin "23") (pinfunction "A0_23") (pintype "bidirectional"))
      (node (ref "IC8") (pin "10") (pinfunction "PF0_10") (pintype "bidirectional"))
    )
    (net (code "31") (name "/DRAM_A1") (class "Default")
      (node (ref "IC2") (pin "24") (pinfunction "A1_24") (pintype "bidirectional"))
      (node (ref "IC8") (pin "11") (pinfunction "PF1_11") (pintype "bidirectional"))
    )
    (net (code "32") (name "/DRAM_A2") (class "Default")
      (node (ref "IC2") (pin "25") (pinfunction "A2_25") (pintype "bidirectional"))
      (node (ref "IC8") (pin "12") (pinfunction "PF2_12") (pintype "bidirectional"))
    )
    (net (code "33") (name "/DRAM_A3") (class "Default")
      (node (ref "IC2") (pin "26") (pinfunction "A3_26") (pintype "bidirectional"))
      (node (ref "IC8") (pin "13") (pinfunction "PF3_13") (pintype "bidirectional"))
    )
    (net (code "34") (name "/DRAM_A4") (class "Default")
      (node (ref "IC2") (pin "29") (pinfunction "A4_29") (pintype "bidirectional"))
      (node (ref "IC8") (pin "14") (pinfunction "PF4_14") (pintype "bidirectional"))
    )
    (net (code "35") (name "/DRAM_A5") (class "Default")
      (node (ref "IC2") (pin "30") (pinfunction "A5_30") (pintype "bidirectional"))
      (node (ref "IC8") (pin "15") (pinfunction "PF5_15") (pintype "bidirectional"))
    )
    (net (code "36") (name "/DRAM_A6") (class "Default")
      (node (ref "IC2") (pin "31") (pinfunction "A6_31") (pintype "bidirectional"))
      (node (ref "IC8") (pin "50") (pinfunction "PF12_50") (pintype "bidirectional"))
    )
    (net (code "37") (name "/DRAM_A7") (class "Default")
      (node (ref "IC2") (pin "32") (pinfunction "A7_32") (pintype "bidirectional"))
      (node (ref "IC8") (pin "53") (pinfunction "PF13_53") (pintype "bidirectional"))
    )
    (net (code "38") (name "/DRAM_A8") (class "Default")
      (node (ref "IC2") (pin "33") (pinfunction "A8_33") (pintype "bidirectional"))
      (node (ref "IC8") (pin "54") (pinfunction "PF14_54") (pintype "bidirectional"))
    )
    (net (code "39") (name "/DRAM_A9") (class "Default")
      (node (ref "IC2") (pin "34") (pinfunction "A9_34") (pintype "bidirectional"))
      (node (ref "IC8") (pin "55") (pinfunction "PF15_55") (pintype "bidirectional"))
    )
    (net (code "40") (name "/DRAM_A10") (class "Default")
      (node (ref "IC2") (pin "22") (pinfunction "A10_22") (pintype "bidirectional"))
      (node (ref "IC8") (pin "56") (pinfunction "PG0_56") (pintype "bidirectional"))
    )
    (net (code "41") (name "/DRAM_A11") (class "Default")
      (node (ref "IC2") (pin "35") (pinfunction "A11_35") (pintype "bidirectional"))
      (node (ref "IC8") (pin "57") (pinfunction "PG1_57") (pintype "bidirectional"))
    )
    (net (code "42") (name "/DRAM_BA0") (class "Default")
      (node (ref "IC2") (pin "20") (pinfunction "BA0_20") (pintype "bidirectional"))
      (node (ref "IC8") (pin "89") (pinfunction "PG4_89") (pintype "bidirectional"))
    )
    (net (code "43") (name "/DRAM_BA1") (class "Default")
      (node (ref "IC2") (pin "21") (pinfunction "BA1_21") (pintype "bidirectional"))
      (node (ref "IC8") (pin "90") (pinfunction "PG5_90") (pintype "bidirectional"))
    )
    (net (code "44") (name "/DRAM_CKE") (class "Default")
      (node (ref "IC2") (pin "37") (pinfunction "CKE_37") (pintype "bidirectional"))
      (node (ref "IC8") (pin "135") (pinfunction "PB5_135") (pintype "bidirectional"))
    )
    (net (code "45") (name "/DRAM_CLK") (class "Default")
      (node (ref "IC2") (pin "38") (pinfunction "CLK_38") (pintype "bidirectional"))
      (node (ref "IC8") (pin "93") (pinfunction "PG8_93") (pintype "bidirectional"))
    )
    (net (code "46") (name "/DRAM_DQ0") (class "Default")
      (node (ref "IC2") (pin "2") (pinfunction "DQ0_2") (pintype "bidirectional"))
      (node (ref "IC8") (pin "85") (pinfunction "PD14_85") (pintype "bidirectional"))
    )
    (net (code "47") (name "/DRAM_DQ1") (class "Default")
      (node (ref "IC2") (pin "4") (pinfunction "DQ1_4") (pintype "bidirectional"))
      (node (ref "IC8") (pin "86") (pinfunction "PD15_86") (pintype "bidirectional"))
    )
    (net (code "48") (name "/DRAM_DQ2") (class "Default")
      (node (ref "IC2") (pin "5") (pinfunction "DQ2_5") (pintype "bidirectional"))
      (node (ref "IC8") (pin "114") (pinfunction "PD0_114") (pintype "bidirectional"))
    )
    (net (code "49") (name "/DRAM_DQ3") (class "Default")
      (node (ref "IC2") (pin "7") (pinfunction "DQ3_7") (pintype "bidirectional"))
      (node (ref "IC8") (pin "115") (pinfunction "PD1_115") (pintype "bidirectional"))
    )
    (net (code "50") (name "/DRAM_DQ4") (class "Default")
      (node (ref "IC2") (pin "8") (pinfunction "DQ4_8") (pintype "bidirectional"))
      (node (ref "IC8") (pin "58") (pinfunction "PE7_58") (pintype "bidirectional"))
    )
    (net (code "51") (name "/DRAM_DQ5") (class "Default")
      (node (ref "IC2") (pin "10") (pinfunction "DQ5_10") (pintype "bidirectional"))
      (node (ref "IC8") (pin "59") (pinfunction "PE8_59") (pintype "bidirectional"))
    )
    (net (code "52") (name "/DRAM_DQ6") (class "Default")
      (node (ref "IC2") (pin "11") (pinfunction "DQ6_11") (pintype "bidirectional"))
      (node (ref "IC8") (pin "60") (pinfunction "PE9_60") (pintype "bidirectional"))
    )
    (net (code "53") (name "/DRAM_DQ7") (class "Default")
      (node (ref "IC2") (pin "13") (pinfunction "DQ7_13") (pintype "bidirectional"))
      (node (ref "IC8") (pin "63") (pinfunction "PE10_63") (pintype "bidirectional"))
    )
    (net (code "54") (name "/DRAM_DQ8") (class "Default")
      (node (ref "IC2") (pin "42") (pinfunction "DQ8_42") (pintype "bidirectional"))
      (node (ref "IC8") (pin "64") (pinfunction "PE11_64") (pintype "bidirectional"))
    )
    (net (code "55") (name "/DRAM_DQ9") (class "Default")
      (node (ref "IC2") (pin "44") (pinfunction "DQ9_44") (pintype "bidirectional"))
      (node (ref "IC8") (pin "65") (pinfunction "PE12_65") (pintype "bidirectional"))
    )
    (net (code "56") (name "/DRAM_DQ10") (class "Default")
      (node (ref "IC2") (pin "45") (pinfunction "DQ10_45") (pintype "bidirectional"))
      (node (ref "IC8") (pin "66") (pinfunction "PE13_66") (pintype "bidirectional"))
    )
    (net (code "57") (name "/DRAM_DQ11") (class "Default")
      (node (ref "IC2") (pin "47") (pinfunction "DQ11_47") (pintype "bidirectional"))
      (node (ref "IC8") (pin "67") (pinfunction "PE14_67") (pintype "bidirectional"))
    )
    (net (code "58") (name "/DRAM_DQ12") (class "Default")
      (node (ref "IC2") (pin "48") (pinfunction "DQ12_48") (pintype "bidirectional"))
      (node (ref "IC8") (pin "68") (pinfunction "PE15_68") (pintype "bidirectional"))
    )
    (net (code "59") (name "/DRAM_DQ13") (class "Default")
      (node (ref "IC2") (pin "50") (pinfunction "DQ13_50") (pintype "bidirectional"))
      (node (ref "IC8") (pin "77") (pinfunction "PD8_77") (pintype "bidirectional"))
    )
    (net (code "60") (name "/DRAM_DQ14") (class "Default")
      (node (ref "IC2") (pin "51") (pinfunction "DQ14_51") (pintype "bidirectional"))
      (node (ref "IC8") (pin "78") (pinfunction "PD9_78") (pintype "bidirectional"))
    )
    (net (code "61") (name "/DRAM_DQ15") (class "Default")
      (node (ref "IC2") (pin "53") (pinfunction "DQ15_53") (pintype "bidirectional"))
      (node (ref "IC8") (pin "79") (pinfunction "PD10_79") (pintype "bidirectional"))
    )
    (net (code "62") (name "/DRAM_LDQM") (class "Default")
      (node (ref "IC2") (pin "15") (pinfunction "LDQM_15") (pintype "bidirectional"))
      (node (ref "IC8") (pin "141") (pinfunction "PE0_141") (pintype "bidirectional"))
    )
    (net (code "63") (name "/DRAM_UDQM") (class "Default")
      (node (ref "IC2") (pin "39") (pinfunction "UDQM_39") (pintype "bidirectional"))
      (node (ref "IC8") (pin "142") (pinfunction "PE1_142") (pintype "bidirectional"))
    )
    (net (code "64") (name "/DRAM_~{CAS}") (class "Default")
      (node (ref "IC2") (pin "17") (pinfunction "~{CAS}_17") (pintype "bidirectional"))
      (node (ref "IC8") (pin "132") (pinfunction "PG15_132") (pintype "bidirectional"))
    )
    (net (code "65") (name "/DRAM_~{CS}") (class "Default")
      (node (ref "IC2") (pin "19") (pinfunction "~{CS}_19") (pintype "bidirectional"))
      (node (ref "IC8") (pin "136") (pinfunction "PB6_136") (pintype "bidirectional"))
    )
    (net (code "66") (name "/DRAM_~{RAS}") (class "Default")
      (node (ref "IC2") (pin "18") (pinfunction "~{RAS}_18") (pintype "bidirectional"))
      (node (ref "IC8") (pin "49") (pinfunction "PF11_49") (pintype "bidirectional"))
    )
    (net (code "67") (name "/DRAM_~{WE}") (class "Default")
      (node (ref "IC2") (pin "16") (pinfunction "~{WE}_16") (pintype "bidirectional"))
      (node (ref "IC8") (pin "26") (pinfunction "PC0_26") (pintype "bidirectional"))
    )
    (net (code "68") (name "/ENC1_A") (class "Default")
      (node (ref "IC8") (pin "42") (pinfunction "PA6_42") (pintype "bidirectional"))
      (node (ref "JP4") (pin "2") (pinfunction "2_2") (pintype "passive"))
    )
    (net (code "69") (name "/ENC1_B") (class "Default")
      (node (ref "IC8") (pin "43") (pinfunction "PA7_43") (pintype "bidirectional"))
      (node (ref "JP4") (pin "3") (pinfunction "3_3") (pintype "passive"))
    )
    (net (code "70") (name "/ENC1_SW") (class "Default")
      (node (ref "IC8") (pin "129") (pinfunction "PG14_129") (pintype "bidirectional"))
      (node (ref "JP4") (pin "1") (pinfunction "1_1") (pintype "passive"))
    )
    (net (code "71") (name "/ENC2_A") (class "Default")
      (node (ref "IC8") (pin "110") (pinfunction "PA15_110") (pintype "bidirectional"))
      (node (ref "JP4") (pin "5") (pinfunction "5_5") (pintype "passive"))
    )
    (net (code "72") (name "/ENC2_B") (class "Default")
      (node (ref "IC8") (pin "133") (pinfunction "PB3_133") (pintype "bidirectional"))
      (node (ref "JP4") (pin "6") (pinfunction "6_6") (pintype "passive"))
    )
    (net (code "73") (name "/ENC2_SW") (class "Default")
      (node (ref "IC8") (pin "134") (pinfunction "PB4_134") (pintype "bidirectional"))
      (node (ref "JP4") (pin "4") (pinfunction "4_4") (pintype "passive"))
    )
    (net (code "74") (name "/FLASH_CLK") (class "Default")
      (node (ref "IC8") (pin "19") (pinfunction "PF7_19") (pintype "bidirectional"))
      (node (ref "IC9") (pin "6") (pinfunction "C_6") (pintype "bidirectional"))
    )
    (net (code "75") (name "/FLASH_HOLD") (class "Default")
      (node (ref "IC8") (pin "22") (pinfunction "PF10_22") (pintype "bidirectional"))
      (node (ref "IC9") (pin "7") (pinfunction "HOLD#/DQ3_7") (pintype "bidirectional"))
    )
    (net (code "76") (name "/FLASH_MISO") (class "Default")
      (node (ref "IC8") (pin "20") (pinfunction "PF8_20") (pintype "bidirectional"))
      (node (ref "IC9") (pin "2") (pinfunction "DQ1_2") (pintype "bidirectional"))
    )
    (net (code "77") (name "/FLASH_MOSI") (class "Default")
      (node (ref "IC8") (pin "21") (pinfunction "PF9_21") (pintype "bidirectional"))
      (node (ref "IC9") (pin "5") (pinfunction "DQ0_5") (pintype "bidirectional"))
    )
    (net (code "78") (name "/FLASH_NCS") (class "Default")
      (node (ref "IC8") (pin "18") (pinfunction "PF6_18") (pintype "bidirectional"))
      (node (ref "IC9") (pin "1") (pinfunction "S#_1") (pintype "bidirectional"))
      (node (ref "R901") (pin "2") (pinfunction "2_2") (pintype "passive"))
    )
    (net (code "79") (name "/FLASH_W") (class "Default")
      (node (ref "IC8") (pin "7") (pinfunction "PC13_7") (pintype "bidirectional"))
      (node (ref "IC9") (pin "3") (pinfunction "VPP/W#/DQ2_3") (pintype "bidirectional"))
    )
    (net (code "80") (name "/INL") (class "Default")
      (node (ref "JP1") (pin "2") (pinfunction "2_2") (pintype "passive"))
      (node (ref "R502") (pin "1") (pinfunction "1_1") (pintype "passive"))
    )
    (net (code "81") (name "/INR") (class "Default")
      (node (ref "JP1") (pin "1") (pinfunction "1_1") (pintype "passive"))
      (node (ref "R507") (pin "1") (pinfunction "1_1") (pintype "passive"))
    )
    (net (code "82") (name "/NRST") (class "Default")
      (node (ref "IC8") (pin "25") (pinfunction "NRST_25") (pintype "bidirectional"))
      (node (ref "X1") (pin "5") (pinfunction "S_5") (pintype "passive"))
    )
    (net (code "83") (name "/OLED_CS") (class "Default")
      (node (ref "IC8") (pin "70") (pinfunction "PB11_70") (pintype "bidirectional"))
      (node (ref "X4") (pin "8") (pinfunction "1_8") (pintype "passive"))
    )
    (net (code "84") (name "/OLED_DC") (class "Default")
      (node (ref "IC8") (pin "29") (pinfunction "PC3_29") (pintype "bidirectional"))
      (node (ref "X4") (pin "10") (pinfunction "1_10") (pintype "passive"))
    )
    (net (code "85") (name "/OLED_MOSI") (class "Default")
      (node (ref "IC8") (pin "27") (pinfunction "PC1_27") (pintype "bidirectional"))
      (node (ref "X4") (pin "14") (pinfunction "1_14") (pintype "passive"))
    )
    (net (code "86") (name "/OLED_RST") (class "Default")
      (node (ref "IC8") (pin "28") (pinfunction "PC2_28") (pintype "bidirectional"))
      (node (ref "X4") (pin "9") (pinfunction "1_9") (pintype "passive"))
    )
    (net (code "87") (name "/OLED_SCK") (class "Default")
      (node (ref "IC8") (pin "69") (pinfunction "PB10_69") (pintype "bidirectional"))
      (node (ref "X4") (pin "13") (pinfunction "1_13") (pintype "passive"))
    )
    (net (code "88") (name "/OUTL") (class "Default")
      (node (ref "JP3") (pin "2") (pinfunction "2_2") (pintype "passive"))
      (node (ref "R604") (pin "1") (pinfunction "1_1") (pintype "passive"))
    )
    (net (code "89") (name "/OUTR") (class "Default")
      (node (ref "JP3") (pin "1") (pinfunction "1_1") (pintype "passive"))
      (node (ref "R611") (pin "1") (pinfunction "1_1") (pintype "passive"))
    )
    (net (code "90") (name "/SWCLK") (class "Default")
      (node (ref "IC8") (pin "109") (pinfunction "PA14_109") (pintype "bidirectional"))
      (node (ref "X1") (pin "2") (pinfunction "S_2") (pintype "passive"))
    )
    (net (code "91") (name "/SWDIO") (class "Default")
      (node (ref "IC8") (pin "105") (pinfunction "PA13_105") (pintype "bidirectional"))
      (node (ref "X1") (pin "4") (pinfunction "S_4") (pintype "passive"))
    )
    (net (code "92") (name "/SW_A") (class "Default")
      (node (ref "IC8") (pin "111") (pinfunction "PC10_111") (pintype "bidirectional"))
      (node (ref "JP1") (pin "8") (pinfunction "8_8") (pintype "passive"))
    )
    (net (code "93") (name "/SW_B") (class "Default")
      (node (ref "IC8") (pin "113") (pinfunction "PC12_113") (pintype "bidirectional"))
      (node (ref "JP3") (pin "8") (pinfunction "8_8") (pintype "passive"))
    )
    (net (code "94") (name "/TRINA") (class "Default")
      (node (ref "JP1") (pin "7") (pinfunction "7_7") (pintype "passive"))
      (node (ref "R14") (pin "1") (pinfunction "1_1") (pintype "passive"))
    )
    (net (code "95") (name "/TRINB") (class "Default")
      (node (ref "JP1") (pin "6") (pinfunction "6_6") (pintype "passive"))
      (node (ref "R10") (pin "1") (pinfunction "1_1") (pintype "passive"))
    )
    (net (code "96") (name "/TROUTA") (class "Default")
      (node (ref "JP3") (pin "7") (pinfunction "7_7") (pintype "passive"))
      (node (ref "R903") (pin "2") (pinfunction "2_2") (pintype "passive"))
      (node (ref "R904") (pin "2") (pinfunction "2_2") (pintype "passive"))
    )
    (net (code "97") (name "/TROUTB") (class "Default")
      (node (ref "JP3") (pin "6") (pinfunction "6_6") (pintype "passive"))
      (node (ref "R703") (pin "2") (pinfunction "2_2") (pintype "passive"))
      (node (ref "R704") (pin "2") (pinfunction "2_2") (pintype "passive"))
    )
    (net (code "98") (name "/TR_IN_A") (class "Default")
      (node (ref "IC8") (pin "112") (pinfunction "PC11_112") (pintype "bidirectional"))
      (node (ref "Q801") (pin "3") (pinfunction "C_3") (pintype "passive"))
      (node (ref "R803") (pin "2") (pinfunction "2_2") (pintype "passive"))
    )
    (net (code "99") (name "/TR_IN_B") (class "Default")
      (node (ref "IC8") (pin "116") (pinfunction "PD2_116") (pintype "bidirectional"))
      (node (ref "Q601") (pin "3") (pinfunction "C_3") (pintype "passive"))
      (node (ref "R11") (pin "2") (pinfunction "2_2") (pintype "passive"))
    )
    (net (code "100") (name "/TR_OUT_A") (class "Default")
      (node (ref "IC8") (pin "118") (pinfunction "PD4_118") (pintype "bidirectional"))
      (node (ref "R13") (pin "2") (pinfunction "2_2") (pintype "passive"))
    )
    (net (code "101") (name "/TR_OUT_B") (class "Default")
      (node (ref "IC8") (pin "117") (pinfunction "PD3_117") (pintype "bidirectional"))
      (node (ref "R701") (pin "2") (pinfunction "2_2") (pintype "passive"))
    )
    (net (code "102") (name "/UART5_RX") (class "Default")
      (node (ref "IC8") (pin "73") (pinfunction "PB12_73") (pintype "bidirectional"))
      (node (ref "JP2") (pin "4") (pinfunction "4_4") (pintype "passive"))
    )
    (net (code "103") (name "/UART5_TX") (class "Default")
      (node (ref "IC8") (pin "74") (pinfunction "PB13_74") (pintype "bidirectional"))
      (node (ref "JP2") (pin "5") (pinfunction "5_5") (pintype "passive"))
    )
    (net (code "104") (name "/UART_MCU_RX") (class "Default")
      (node (ref "BUS") (pin "1") (pinfunction "1_1") (pintype "passive"))
      (node (ref "IC8") (pin "37") (pinfunction "PA3_37") (pintype "bidirectional"))
    )
    (net (code "105") (name "/UART_MCU_TX") (class "Default")
      (node (ref "BUS") (pin "3") (pinfunction "3_3") (pintype "passive"))
      (node (ref "IC8") (pin "36") (pinfunction "PA2_36") (pintype "bidirectional"))
    )
    (net (code "106") (name "/USBD_DM") (class "Default")
      (node (ref "IC10") (pin "1") (pinfunction "I/O_1_1") (pintype "bidirectional"))
      (node (ref "IC8") (pin "103") (pinfunction "PA11_103") (pintype "bidirectional"))
    )
    (net (code "107") (name "/USBD_DP") (class "Default")
      (node (ref "IC10") (pin "3") (pinfunction "I/O_2_3") (pintype "bidirectional"))
      (node (ref "IC8") (pin "104") (pinfunction "PA12_104") (pintype "bidirectional"))
    )
    (net (code "108") (name "/USBD_VBUS") (class "Default")
      (node (ref "IC10") (pin "5") (pinfunction "VBUS_5") (pintype "bidirectional"))
      (node (ref "IC8") (pin "101") (pinfunction "PA9_101") (pintype "bidirectional"))
      (node (ref "JP2") (pin "1") (pinfunction "1_1") (pintype "passive"))
    )
    (net (code "109") (name "/USBH_DM") (class "Default")
      (node (ref "IC8") (pin "75") (pinfunction "PB14_75") (pintype "bidirectional"))
      (node (ref "JP2") (pin "7") (pinfunction "7_7") (pintype "passive"))
    )
    (net (code "110") (name "/USBH_DP") (class "Default")
      (node (ref "IC8") (pin "76") (pinfunction "PB15_76") (pintype "bidirectional"))
      (node (ref "JP2") (pin "8") (pinfunction "8_8") (pintype "passive"))
    )
    (net (code "111") (name "/USBH_PWR_EN") (class "Default")
      (node (ref "IC7") (pin "3") (pinfunction "EN_3") (pintype "input"))
      (node (ref "IC8") (pin "99") (pinfunction "PC9_99") (pintype "bidirectional"))
    )
    (net (code "112") (name "/USBH_PWR_FAULT") (class "Default")
      (node (ref "IC7") (pin "4") (pinfunction "FAULT_4") (pintype "output"))
      (node (ref "IC8") (pin "102") (pinfunction "PA10_102") (pintype "bidirectional"))
    )
    (net (code "113") (name "/USBH_VBUS") (class "Default")
      (node (ref "IC7") (pin "6") (pinfunction "VOUT_6") (pintype "output"))
      (node (ref "JP2") (pin "6") (pinfunction "6_6") (pintype "passive"))
    )
    (net (code "114") (name "/VDDA") (class "Default")
      (node (ref "C24") (pin "1") (pinfunction "1_1") (pintype "passive"))
      (node (ref "C27") (pin "1") (pinfunction "1_1") (pintype "passive"))
      (node (ref "IC8") (pin "33") (pinfunction "VDDA_33") (pintype "bidirectional"))
      (node (ref "L2") (pin "1") (pinfunction "1_1") (pintype "passive"))
    )
    (net (code "115") (name "GND") (class "Default")
      (node (ref "BUS") (pin "2") (pinfunction "2_2") (pintype "passive"))
      (node (ref "C10") (pin "2") (pinfunction "2_2") (pintype "passive"))
      (node (ref "C11") (pin "2") (pinfunction "2_2") (pintype "passive"))
      (node (ref "C110") (pin "1") (pinfunction "1_1") (pintype "passive"))
      (node (ref "C111") (pin "-") (pinfunction "-_-") (pintype "passive"))
      (node (ref "C112") (pin "2") (pinfunction "2_2") (pintype "passive"))
      (node (ref "C12") (pin "2") (pinfunction "2_2") (pintype "passive"))
      (node (ref "C13") (pin "2") (pinfunction "2_2") (pintype "passive"))
      (node (ref "C14") (pin "2") (pinfunction "2_2") (pintype "passive"))
      (node (ref "C15") (pin "2") (pinfunction "2_2") (pintype "passive"))
      (node (ref "C16") (pin "2") (pinfunction "2_2") (pintype "passive"))
      (node (ref "C17") (pin "2") (pinfunction "2_2") (pintype "passive"))
      (node (ref "C18") (pin "2") (pinfunction "2_2") (pintype "passive"))
      (node (ref "C19") (pin "2") (pinfunction "2_2") (pintype "passive"))
      (node (ref "C20") (pin "2") (pinfunction "2_2") (pintype "passive"))
      (node (ref "C21") (pin "2") (pinfunction "2_2") (pintype "passive"))
      (node (ref "C22") (pin "2") (pinfunction "2_2") (pintype "passive"))
      (node (ref "C24") (pin "2") (pinfunction "2_2") (pintype "passive"))
      (node (ref "C27") (pin "2") (pinfunction "2_2") (pintype "passive"))
      (node (ref "C29") (pin "1") (pinfunction "1_1") (pintype "passive"))
      (node (ref "C30") (pin "1") (pinfunction "1_1") (pintype "passive"))
      (node (ref "C31") (pin "C") (pinfunction "-_C") (pintype "passive"))
      (node (ref "C32") (pin "1") (pinfunction "1_1") (pintype "passive"))
      (node (ref "C33") (pin "2") (pinfunction "2_2") (pintype "passive"))
      (node (ref "C34") (pin "2") (pinfunction "2_2") (pintype "passive"))
      (node (ref "C35") (pin "2") (pinfunction "2_2") (pintype "passive"))
      (node (ref "C36") (pin "1") (pinfunction "1_1") (pintype "passive"))
      (node (ref "C37") (pin "2") (pinfunction "2_2") (pintype "passive"))
      (node (ref "C38") (pin "2") (pinfunction "2_2") (pintype "passive"))
      (node (ref "C39") (pin "2") (pinfunction "2_2") (pintype "passive"))
      (node (ref "C40") (pin "2") (pinfunction "2_2") (pintype "passive"))
      (node (ref "C401") (pin "2") (pinfunction "2_2") (pintype "passive"))
      (node (ref "C402") (pin "2") (pinfunction "2_2") (pintype "passive"))
      (node (ref "C403") (pin "2") (pinfunction "2_2") (pintype "passive"))
      (node (ref "C404") (pin "2") (pinfunction "2_2") (pintype "passive"))
      (node (ref "C405") (pin "2") (pinfunction "2_2") (pintype "passive"))
      (node (ref "C406") (pin "2") (pinfunction "2_2") (pintype "passive"))
      (node (ref "C407") (pin "2") (pinfunction "2_2") (pintype "passive"))
      (node (ref "C408") (pin "2") (pinfunction "2_2") (pintype "passive"))
      (node (ref "C409") (pin "-") (pinfunction "-_-") (pintype "passive"))
      (node (ref "C41") (pin "2") (pinfunction "2_2") (pintype "passive"))
      (node (ref "C410") (pin "2") (pinfunction "2_2") (pintype "passive"))
      (node (ref "C411") (pin "2") (pinfunction "2_2") (pintype "passive"))
      (node (ref "C412") (pin "-") (pinfunction "-_-") (pintype "passive"))
      (node (ref "C414") (pin "2") (pinfunction "2_2") (pintype "passive"))
      (node (ref "C42") (pin "2") (pinfunction "2_2") (pintype "passive"))
      (node (ref "C43") (pin "2") (pinfunction "2_2") (pintype "passive"))
      (node (ref "C5") (pin "2") (pinfunction "2_2") (pintype "passive"))
      (node (ref "C503") (pin "2") (pinfunction "2_2") (pintype "passive"))
      (node (ref "C504") (pin "2") (pinfunction "2_2") (pintype "passive"))
      (node (ref "C6") (pin "2") (pinfunction "2_2") (pintype "passive"))
      (node (ref "C601") (pin "1") (pinfunction "1_1") (pintype "passive"))
      (node (ref "C603") (pin "2") (pinfunction "2_2") (pintype "passive"))
      (node (ref "C604") (pin "2") (pinfunction "2_2") (pintype "passive"))
      (node (ref "C605") (pin "2") (pinfunction "2_2") (pintype "passive"))
      (node (ref "C606") (pin "2") (pinfunction "2_2") (pintype "passive"))
      (node (ref "C607") (pin "1") (pinfunction "1_1") (pintype "passive"))
      (node (ref "C609") (pin "2") (pinfunction "2_2") (pintype "passive"))
      (node (ref "C610") (pin "2") (pinfunction "2_2") (pintype "passive"))
      (node (ref "C7") (pin "2") (pinfunction "2_2") (pintype "passive"))
      (node (ref "C8") (pin "2") (pinfunction "2_2") (pintype "passive"))
      (node (ref "C802") (pin "1") (pinfunction "1_1") (pintype "passive"))
      (node (ref "C9") (pin "2") (pinfunction "2_2") (pintype "passive"))
      (node (ref "C901") (pin "2") (pinfunction "2_2") (pintype "passive"))
      (node (ref "D3") (pin "1") (pinfunction "A1_1") (pintype "passive"))
      (node (ref "D4") (pin "1") (pinfunction "A1_1") (pintype "passive"))
      (node (ref "IC10") (pin "2") (pinfunction "GND_2") (pintype "bidirectional"))
      (node (ref "IC2") (pin "12") (pinfunction "GNDQ1_12") (pintype "bidirectional"))
      (node (ref "IC2") (pin "28") (pinfunction "GND1_28") (pintype "bidirectional"))
      (node (ref "IC2") (pin "41") (pinfunction "GND_41") (pintype "bidirectional"))
      (node (ref "IC2") (pin "46") (pinfunction "GNDQ2_46") (pintype "bidirectional"))
      (node (ref "IC2") (pin "52") (pinfunction "GNDQ3_52") (pintype "bidirectional"))
      (node (ref "IC2") (pin "54") (pinfunction "GND2_54") (pintype "bidirectional"))
      (node (ref "IC2") (pin "6") (pinfunction "GNDQ_6") (pintype "bidirectional"))
      (node (ref "IC4") (pin "21") (pinfunction "AGND_21") (pintype "bidirectional"))
      (node (ref "IC4") (pin "8") (pinfunction "DGND_8") (pintype "bidirectional"))
      (node (ref "IC7") (pin "2") (pinfunction "GND_2") (pintype "power_in"))
      (node (ref "IC8") (pin "107") (pinfunction "VSS6_107") (pintype "bidirectional"))
      (node (ref "IC8") (pin "120") (pinfunction "VSS7_120") (pintype "bidirectional"))
      (node (ref "IC8") (pin "130") (pinfunction "VSS8_130") (pintype "bidirectional"))
      (node (ref "IC8") (pin "143") (pinfunction "PDR_ON_143") (pintype "bidirectional"))
      (node (ref "IC8") (pin "16") (pinfunction "VSS_16") (pintype "bidirectional"))
      (node (ref "IC8") (pin "31") (pinfunction "VSSA_31") (pintype "bidirectional"))
      (node (ref "IC8") (pin "38") (pinfunction "VSS1_38") (pintype "bidirectional"))
      (node (ref "IC8") (pin "51") (pinfunction "VSS2_51") (pintype "bidirectional"))
      (node (ref "IC8") (pin "61") (pinfunction "VSS3_61") (pintype "bidirectional"))
      (node (ref "IC8") (pin "83") (pinfunction "VSS4_83") (pintype "bidirectional"))
      (node (ref "IC8") (pin "94") (pinfunction "VSS5_94") (pintype "bidirectional"))
      (node (ref "IC9") (pin "4") (pinfunction "VSS_4") (pintype "bidirectional"))
      (node (ref "JP1") (pin "4") (pinfunction "4_4") (pintype "passive"))
      (node (ref "JP2") (pin "9") (pinfunction "9_9") (pintype "passive"))
      (node (ref "JP3") (pin "4") (pinfunction "4_4") (pintype "passive"))
      (node (ref "JP4") (pin "9") (pinfunction "9_9") (pintype "passive"))
      (node (ref "PWR") (pin "3") (pinfunction "3_3") (pintype "passive"))
      (node (ref "PWR") (pin "4") (pinfunction "4_4") (pintype "passive"))
      (node (ref "PWR") (pin "5") (pinfunction "5_5") (pintype "passive"))
      (node (ref "PWR") (pin "6") (pinfunction "6_6") (pintype "passive"))
      (node (ref "PWR") (pin "7") (pinfunction "7_7") (pintype "passive"))
      (node (ref "PWR") (pin "8") (pinfunction "8_8") (pintype "passive"))
      (node (ref "Q1") (pin "1") (pinfunction "G_1") (pintype "passive"))
      (node (ref "Q2") (pin "1") (pinfunction "G_1") (pintype "passive"))
      (node (ref "Q601") (pin "2") (pinfunction "E_2") (pintype "passive"))
      (node (ref "Q701") (pin "2") (pinfunction "E_2") (pintype "passive"))
      (node (ref "Q801") (pin "2") (pinfunction "E_2") (pintype "passive"))
      (node (ref "Q903") (pin "2") (pinfunction "E_2") (pintype "passive"))
      (node (ref "R12") (pin "2") (pinfunction "2_2") (pintype "passive"))
      (node (ref "R15") (pin "2") (pinfunction "2_2") (pintype "passive"))
      (node (ref "R16") (pin "2") (pinfunction "2_2") (pintype "passive"))
      (node (ref "R17") (pin "1") (pinfunction "1_1") (pintype "passive"))
      (node (ref "R18") (pin "1") (pinfunction "1_1") (pintype "passive"))
      (node (ref "R3") (pin "1") (pinfunction "1_1") (pintype "passive"))
      (node (ref "R402") (pin "1") (pinfunction "1_1") (pintype "passive"))
      (node (ref "R505") (pin "2") (pinfunction "2_2") (pintype "passive"))
      (node (ref "R510") (pin "2") (pinfunction "2_2") (pintype "passive"))
      (node (ref "R607") (pin "2") (pinfunction "2_2") (pintype "passive"))
      (node (ref "R614") (pin "2") (pinfunction "2_2") (pintype "passive"))
      (node (ref "R7") (pin "1") (pinfunction "1_1") (pintype "passive"))
      (node (ref "R704") (pin "1") (pinfunction "1_1") (pintype "passive"))
      (node (ref "R801") (pin "1") (pinfunction "1_1") (pintype "passive"))
      (node (ref "R802") (pin "2") (pinfunction "2_2") (pintype "passive"))
      (node (ref "R9") (pin "1") (pinfunction "1_1") (pintype "passive"))
      (node (ref "R904") (pin "1") (pinfunction "1_1") (pintype "passive"))
      (node (ref "U4") (pin "1") (pinfunction "ADJ_1") (pintype "input"))
      (node (ref "X1") (pin "3") (pinfunction "S_3") (pintype "passive"))
      (node (ref "X4") (pin "1") (pinfunction "1_1") (pintype "passive"))
      (node (ref "X4") (pin "11") (pinfunction "1_11") (pintype "passive"))
      (node (ref "X4") (pin "12") (pinfunction "1_12") (pintype "passive"))
      (node (ref "X4") (pin "16") (pinfunction "1_16") (pintype "passive"))
      (node (ref "X4") (pin "17") (pinfunction "1_17") (pintype "passive"))
      (node (ref "X4") (pin "18") (pinfunction "1_18") (pintype "passive"))
      (node (ref "X4") (pin "19") (pinfunction "1_19") (pintype "passive"))
      (node (ref "X4") (pin "2") (pinfunction "1_2") (pintype "passive"))
      (node (ref "X4") (pin "20") (pinfunction "1_20") (pintype "passive"))
      (node (ref "X4") (pin "24") (pinfunction "1_24") (pintype "passive"))
      (node (ref "X4") (pin "3") (pinfunction "1_3") (pintype "passive"))
      (node (ref "X4") (pin "6") (pinfunction "1_6") (pintype "passive"))
      (node (ref "X4") (pin "7") (pinfunction "1_7") (pintype "passive"))
    )
    (net (code "116") (name "Net-(C31-+)") (class "Default")
      (node (ref "C31") (pin "A") (pinfunction "+_A") (pintype "passive"))
      (node (ref "X4") (pin "22") (pinfunction "1_22") (pintype "passive"))
    )
    (net (code "117") (name "Net-(C601-Pad2)") (class "Default")
      (node (ref "C601") (pin "2") (pinfunction "2_2") (pintype "passive"))
      (node (ref "R601") (pin "2") (pinfunction "2_2") (pintype "passive"))
      (node (ref "R602") (pin "1") (pinfunction "1_1") (pintype "passive"))
      (node (ref "R603") (pin "2") (pinfunction "2_2") (pintype "passive"))
    )
    (net (code "118") (name "Net-(C603-Pad1)") (class "Default")
      (node (ref "C603") (pin "1") (pinfunction "1_1") (pintype "passive"))
      (node (ref "R605") (pin "1") (pinfunction "1_1") (pintype "passive"))
      (node (ref "R606") (pin "2") (pinfunction "2_2") (pintype "passive"))
      (node (ref "R607") (pin "1") (pinfunction "1_1") (pintype "passive"))
    )
    (net (code "119") (name "Net-(C607-Pad2)") (class "Default")
      (node (ref "C607") (pin "2") (pinfunction "2_2") (pintype "passive"))
      (node (ref "R608") (pin "2") (pinfunction "2_2") (pintype "passive"))
      (node (ref "R609") (pin "1") (pinfunction "1_1") (pintype "passive"))
      (node (ref "R610") (pin "2") (pinfunction "2_2") (pintype "passive"))
    )
    (net (code "120") (name "Net-(C609-Pad1)") (class "Default")
      (node (ref "C609") (pin "1") (pinfunction "1_1") (pintype "passive"))
      (node (ref "R612") (pin "1") (pinfunction "1_1") (pintype "passive"))
      (node (ref "R613") (pin "2") (pinfunction "2_2") (pintype "passive"))
      (node (ref "R614") (pin "1") (pinfunction "1_1") (pintype "passive"))
    )
    (net (code "121") (name "Net-(D3-C1A2)") (class "Default")
      (node (ref "C14") (pin "1") (pinfunction "1_1") (pintype "passive"))
      (node (ref "D3") (pin "3") (pinfunction "C1A2_3") (pintype "passive"))
      (node (ref "R15") (pin "1") (pinfunction "1_1") (pintype "passive"))
      (node (ref "R21") (pin "1") (pinfunction "1_1") (pintype "passive"))
      (node (ref "R22") (pin "2") (pinfunction "2_2") (pintype "passive"))
    )
    (net (code "122") (name "Net-(D4-C1A2)") (class "Default")
      (node (ref "C13") (pin "1") (pinfunction "1_1") (pintype "passive"))
      (node (ref "D4") (pin "3") (pinfunction "C1A2_3") (pintype "passive"))
      (node (ref "R16") (pin "1") (pinfunction "1_1") (pintype "passive"))
      (node (ref "R5") (pin "1") (pinfunction "1_1") (pintype "passive"))
      (node (ref "R8") (pin "2") (pinfunction "2_2") (pintype "passive"))
    )
    (net (code "123") (name "Net-(IC1A-+IN)") (class "Default")
      (node (ref "C16") (pin "1") (pinfunction "1_1") (pintype "passive"))
      (node (ref "IC1") (pin "3") (pinfunction "+IN_3") (pintype "input"))
      (node (ref "R2") (pin "2") (pinfunction "2_2") (pintype "passive"))
    )
    (net (code "124") (name "Net-(IC1A--IN)") (class "Default")
      (node (ref "IC1") (pin "2") (pinfunction "-IN_2") (pintype "input"))
      (node (ref "R6") (pin "1") (pinfunction "1_1") (pintype "passive"))
      (node (ref "R7") (pin "2") (pinfunction "2_2") (pintype "passive"))
    )
    (net (code "125") (name "Net-(IC1A-OUT)") (class "Default")
      (node (ref "IC1") (pin "1") (pinfunction "OUT_1") (pintype "output"))
      (node (ref "R19") (pin "1") (pinfunction "1_1") (pintype "passive"))
      (node (ref "R6") (pin "2") (pinfunction "2_2") (pintype "passive"))
    )
    (net (code "126") (name "Net-(IC1B-+IN)") (class "Default")
      (node (ref "C15") (pin "1") (pinfunction "1_1") (pintype "passive"))
      (node (ref "IC1") (pin "5") (pinfunction "+IN_5") (pintype "input"))
      (node (ref "R1") (pin "2") (pinfunction "2_2") (pintype "passive"))
    )
    (net (code "127") (name "Net-(IC1B--IN)") (class "Default")
      (node (ref "IC1") (pin "6") (pinfunction "-IN_6") (pintype "input"))
      (node (ref "R4") (pin "1") (pinfunction "1_1") (pintype "passive"))
      (node (ref "R9") (pin "2") (pinfunction "2_2") (pintype "passive"))
    )
    (net (code "128") (name "Net-(IC1B-OUT)") (class "Default")
      (node (ref "IC1") (pin "7") (pinfunction "OUT_7") (pintype "output"))
      (node (ref "R20") (pin "1") (pinfunction "1_1") (pintype "passive"))
      (node (ref "R4") (pin "2") (pinfunction "2_2") (pintype "passive"))
    )
    (net (code "129") (name "Net-(IC1C--IN)") (class "Default")
      (node (ref "IC1") (pin "8") (pinfunction "OUT_8") (pintype "output"))
      (node (ref "IC1") (pin "9") (pinfunction "-IN_9") (pintype "input"))
      (node (ref "R22") (pin "1") (pinfunction "1_1") (pintype "passive"))
    )
    (net (code "130") (name "Net-(IC1D--IN)") (class "Default")
      (node (ref "IC1") (pin "13") (pinfunction "-IN_13") (pintype "input"))
      (node (ref "IC1") (pin "14") (pinfunction "OUT_14") (pintype "output"))
      (node (ref "R8") (pin "1") (pinfunction "1_1") (pintype "passive"))
    )
    (net (code "131") (name "Net-(IC4-FILT+)") (class "Default")
      (node (ref "C411") (pin "1") (pinfunction "1_1") (pintype "passive"))
      (node (ref "C412") (pin "+") (pinfunction "+_+") (pintype "passive"))
      (node (ref "IC4") (pin "22") (pinfunction "FILT+_22") (pintype "bidirectional"))
    )
    (net (code "132") (name "Net-(IC4-VA)") (class "Default")
      (node (ref "C407") (pin "1") (pinfunction "1_1") (pintype "passive"))
      (node (ref "C408") (pin "1") (pinfunction "1_1") (pintype "passive"))
      (node (ref "IC4") (pin "20") (pinfunction "VA_20") (pintype "bidirectional"))
      (node (ref "L1") (pin "2") (pinfunction "2_2") (pintype "passive"))
    )
    (net (code "133") (name "Net-(IC4-VD)") (class "Default")
      (node (ref "C405") (pin "1") (pinfunction "1_1") (pintype "passive"))
      (node (ref "C406") (pin "1") (pinfunction "1_1") (pintype "passive"))
      (node (ref "IC4") (pin "9") (pinfunction "VD_9") (pintype "bidirectional"))
      (node (ref "R401") (pin "1") (pinfunction "1_1") (pintype "passive"))
    )
    (net (code "134") (name "Net-(IC4-XTI)") (class "Default")
      (node (ref "C401") (pin "1") (pinfunction "1_1") (pintype "passive"))
      (node (ref "IC4") (pin "2") (pinfunction "XTI_2") (pintype "bidirectional"))
      (node (ref "Y1") (pin "2") (pinfunction "2_2") (pintype "passive"))
    )
    (net (code "135") (name "Net-(IC4-XTO)") (class "Default")
      (node (ref "C402") (pin "1") (pinfunction "1_1") (pintype "passive"))
      (node (ref "IC4") (pin "1") (pinfunction "XTO_1") (pintype "bidirectional"))
      (node (ref "Y1") (pin "1") (pinfunction "1_1") (pintype "passive"))
    )
    (net (code "136") (name "Net-(IC5A-+IN)") (class "Default")
      (node (ref "IC5") (pin "3") (pinfunction "+IN_3") (pintype "input"))
      (node (ref "R504") (pin "2") (pinfunction "2_2") (pintype "passive"))
      (node (ref "R505") (pin "1") (pinfunction "1_1") (pintype "passive"))
    )
    (net (code "137") (name "Net-(IC5A--IN)") (class "Default")
      (node (ref "IC5") (pin "2") (pinfunction "-IN_2") (pintype "input"))
      (node (ref "R501") (pin "1") (pinfunction "1_1") (pintype "passive"))
      (node (ref "R502") (pin "2") (pinfunction "2_2") (pintype "passive"))
    )
    (net (code "138") (name "Net-(IC5A-OUT)") (class "Default")
      (node (ref "IC5") (pin "1") (pinfunction "OUT_1") (pintype "output"))
      (node (ref "R501") (pin "2") (pinfunction "2_2") (pintype "passive"))
      (node (ref "R503") (pin "1") (pinfunction "1_1") (pintype "passive"))
    )
    (net (code "139") (name "Net-(IC5B-+IN)") (class "Default")
      (node (ref "IC5") (pin "5") (pinfunction "+IN_5") (pintype "input"))
      (node (ref "R509") (pin "2") (pinfunction "2_2") (pintype "passive"))
      (node (ref "R510") (pin "1") (pinfunction "1_1") (pintype "passive"))
    )
    (net (code "140") (name "Net-(IC5B--IN)") (class "Default")
      (node (ref "IC5") (pin "6") (pinfunction "-IN_6") (pintype "input"))
      (node (ref "R506") (pin "1") (pinfunction "1_1") (pintype "passive"))
      (node (ref "R507") (pin "2") (pinfunction "2_2") (pintype "passive"))
    )
    (net (code "141") (name "Net-(IC5B-OUT)") (class "Default")
      (node (ref "IC5") (pin "7") (pinfunction "OUT_7") (pintype "output"))
      (node (ref "R506") (pin "2") (pinfunction "2_2") (pintype "passive"))
      (node (ref "R508") (pin "1") (pinfunction "1_1") (pintype "passive"))
    )
    (net (code "142") (name "Net-(IC6A-+IN)") (class "Default")
      (node (ref "C604") (pin "1") (pinfunction "1_1") (pintype "passive"))
      (node (ref "IC6") (pin "3") (pinfunction "+IN_3") (pintype "input"))
      (node (ref "R606") (pin "1") (pinfunction "1_1") (pintype "passive"))
    )
    (net (code "143") (name "Net-(IC6A--IN)") (class "Default")
      (node (ref "C602") (pin "1") (pinfunction "1_1") (pintype "passive"))
      (node (ref "IC6") (pin "2") (pinfunction "-IN_2") (pintype "input"))
      (node (ref "R603") (pin "1") (pinfunction "1_1") (pintype "passive"))
    )
    (net (code "144") (name "Net-(IC6A-OUT)") (class "Default")
      (node (ref "C602") (pin "2") (pinfunction "2_2") (pintype "passive"))
      (node (ref "IC6") (pin "1") (pinfunction "OUT_1") (pintype "output"))
      (node (ref "R601") (pin "1") (pinfunction "1_1") (pintype "passive"))
      (node (ref "R604") (pin "2") (pinfunction "2_2") (pintype "passive"))
    )
    (net (code "145") (name "Net-(IC6B-+IN)") (class "Default")
      (node (ref "C610") (pin "1") (pinfunction "1_1") (pintype "passive"))
      (node (ref "IC6") (pin "5") (pinfunction "+IN_5") (pintype "input"))
      (node (ref "R613") (pin "1") (pinfunction "1_1") (pintype "passive"))
    )
    (net (code "146") (name "Net-(IC6B--IN)") (class "Default")
      (node (ref "C608") (pin "1") (pinfunction "1_1") (pintype "passive"))
      (node (ref "IC6") (pin "6") (pinfunction "-IN_6") (pintype "input"))
      (node (ref "R610") (pin "1") (pinfunction "1_1") (pintype "passive"))
    )
    (net (code "147") (name "Net-(IC6B-OUT)") (class "Default")
      (node (ref "C608") (pin "2") (pinfunction "2_2") (pintype "passive"))
      (node (ref "IC6") (pin "7") (pinfunction "OUT_7") (pintype "output"))
      (node (ref "R608") (pin "1") (pinfunction "1_1") (pintype "passive"))
      (node (ref "R611") (pin "2") (pinfunction "2_2") (pintype "passive"))
    )
    (net (code "148") (name "Net-(IC8A-PH0)") (class "Default")
      (node (ref "C11") (pin "1") (pinfunction "1_1") (pintype "passive"))
      (node (ref "IC8") (pin "23") (pinfunction "PH0_23") (pintype "bidirectional"))
      (node (ref "Y2") (pin "2") (pinfunction "2_2") (pintype "passive"))
    )
    (net (code "149") (name "Net-(IC8A-PH1)") (class "Default")
      (node (ref "C12") (pin "1") (pinfunction "1_1") (pintype "passive"))
      (node (ref "IC8") (pin "24") (pinfunction "PH1_24") (pintype "bidirectional"))
      (node (ref "Y2") (pin "1") (pinfunction "1_1") (pintype "passive"))
    )
    (net (code "150") (name "Net-(IC8B-VCAP_1)") (class "Default")
      (node (ref "C20") (pin "1") (pinfunction "1_1") (pintype "passive"))
      (node (ref "IC8") (pin "71") (pinfunction "VCAP_1_71") (pintype "bidirectional"))
    )
    (net (code "151") (name "Net-(IC8C-VCAP_2)") (class "Default")
      (node (ref "C19") (pin "1") (pinfunction "1_1") (pintype "passive"))
      (node (ref "IC8") (pin "106") (pinfunction "VCAP_2_106") (pintype "bidirectional"))
    )
    (net (code "152") (name "Net-(IC10-I{slash}O1)") (class "Default")
      (node (ref "IC10") (pin "6") (pinfunction "I/O1_6") (pintype "bidirectional"))
      (node (ref "JP2") (pin "2") (pinfunction "2_2") (pintype "passive"))
    )
    (net (code "153") (name "Net-(IC10-I{slash}O2)") (class "Default")
      (node (ref "IC10") (pin "4") (pinfunction "I/O2_4") (pintype "bidirectional"))
      (node (ref "JP2") (pin "3") (pinfunction "3_3") (pintype "passive"))
    )
    (net (code "154") (name "Net-(Q1-D)") (class "Default")
      (node (ref "PWR") (pin "1") (pinfunction "1_1") (pintype "passive"))
      (node (ref "PWR") (pin "2") (pinfunction "2_2") (pintype "passive"))
      (node (ref "Q1") (pin "3") (pinfunction "D_3") (pintype "passive"))
    )
    (net (code "155") (name "Net-(Q2-D)") (class "Default")
      (node (ref "PWR") (pin "10") (pinfunction "10_10") (pintype "passive"))
      (node (ref "PWR") (pin "9") (pinfunction "9_9") (pintype "passive"))
      (node (ref "Q2") (pin "3") (pinfunction "D_3") (pintype "passive"))
    )
    (net (code "156") (name "Net-(Q601-B)") (class "Default")
      (node (ref "Q601") (pin "1") (pinfunction "B_1") (pintype "passive"))
      (node (ref "R10") (pin "2") (pinfunction "2_2") (pintype "passive"))
      (node (ref "R12") (pin "1") (pinfunction "1_1") (pintype "passive"))
    )
    (net (code "157") (name "Net-(Q701-B)") (class "Default")
      (node (ref "Q701") (pin "1") (pinfunction "B_1") (pintype "passive"))
      (node (ref "R701") (pin "1") (pinfunction "1_1") (pintype "passive"))
    )
    (net (code "158") (name "Net-(Q701-C)") (class "Default")
      (node (ref "Q701") (pin "3") (pinfunction "C_3") (pintype "passive"))
      (node (ref "R702") (pin "1") (pinfunction "1_1") (pintype "passive"))
      (node (ref "R703") (pin "1") (pinfunction "1_1") (pintype "passive"))
    )
    (net (code "159") (name "Net-(Q801-B)") (class "Default")
      (node (ref "Q801") (pin "1") (pinfunction "B_1") (pintype "passive"))
      (node (ref "R14") (pin "2") (pinfunction "2_2") (pintype "passive"))
      (node (ref "R802") (pin "1") (pinfunction "1_1") (pintype "passive"))
    )
    (net (code "160") (name "Net-(Q903-B)") (class "Default")
      (node (ref "Q903") (pin "1") (pinfunction "B_1") (pintype "passive"))
      (node (ref "R13") (pin "1") (pinfunction "1_1") (pintype "passive"))
    )
    (net (code "161") (name "Net-(Q903-C)") (class "Default")
      (node (ref "Q903") (pin "3") (pinfunction "C_3") (pintype "passive"))
      (node (ref "R902") (pin "2") (pinfunction "2_2") (pintype "passive"))
      (node (ref "R903") (pin "1") (pinfunction "1_1") (pintype "passive"))
    )
    (net (code "162") (name "Net-(X4N-1)") (class "Default")
      (node (ref "R801") (pin "2") (pinfunction "2_2") (pintype "passive"))
      (node (ref "X4") (pin "21") (pinfunction "1_21") (pintype "passive"))
    )
    (net (code "163") (name "unconnected-(IC4-MCLK-Pad3)") (class "Default")
      (node (ref "IC4") (pin "3") (pinfunction "MCLK_3") (pintype "bidirectional"))
    )
    (net (code "164") (name "unconnected-(IC4-~{AMUTEC}-Pad23)") (class "Default")
      (node (ref "IC4") (pin "23") (pinfunction "~{AMUTEC}_23") (pintype "bidirectional"))
    )
    (net (code "165") (name "unconnected-(IC4-~{BMUTEC}-Pad28)") (class "Default")
      (node (ref "IC4") (pin "28") (pinfunction "~{BMUTEC}_28") (pintype "bidirectional"))
    )
    (net (code "166") (name "unconnected-(IC8A-PB0-Pad46)") (class "Default")
      (node (ref "IC8") (pin "46") (pinfunction "PB0_46") (pintype "bidirectional"))
    )
    (net (code "167") (name "unconnected-(IC8A-PB1-Pad47)") (class "Default")
      (node (ref "IC8") (pin "47") (pinfunction "PB1_47") (pintype "bidirectional"))
    )
    (net (code "168") (name "unconnected-(IC8A-PB2-Pad48)") (class "Default")
      (node (ref "IC8") (pin "48") (pinfunction "PB2_48") (pintype "bidirectional"))
    )
    (net (code "169") (name "unconnected-(IC8A-PC4-Pad44)") (class "Default")
      (node (ref "IC8") (pin "44") (pinfunction "PC4_44") (pintype "bidirectional"))
    )
    (net (code "170") (name "unconnected-(IC8A-PC5-Pad45)") (class "Default")
      (node (ref "IC8") (pin "45") (pinfunction "PC5_45") (pintype "bidirectional"))
    )
    (net (code "171") (name "unconnected-(IC8A-PC14-Pad8)") (class "Default")
      (node (ref "IC8") (pin "8") (pinfunction "PC14_8") (pintype "bidirectional"))
    )
    (net (code "172") (name "unconnected-(IC8A-PC15-Pad9)") (class "Default")
      (node (ref "IC8") (pin "9") (pinfunction "PC15_9") (pintype "bidirectional"))
    )
    (net (code "173") (name "unconnected-(IC8A-VBAT-Pad6)") (class "Default")
      (node (ref "IC8") (pin "6") (pinfunction "VBAT_6") (pintype "bidirectional"))
    )
    (net (code "174") (name "unconnected-(IC8B-PC6-Pad96)") (class "Default")
      (node (ref "IC8") (pin "96") (pinfunction "PC6_96") (pintype "bidirectional"))
    )
    (net (code "175") (name "unconnected-(IC8B-PD11-Pad80)") (class "Default")
      (node (ref "IC8") (pin "80") (pinfunction "PD11_80") (pintype "bidirectional"))
    )
    (net (code "176") (name "unconnected-(IC8B-PD12-Pad81)") (class "Default")
      (node (ref "IC8") (pin "81") (pinfunction "PD12_81") (pintype "bidirectional"))
    )
    (net (code "177") (name "unconnected-(IC8B-PD13-Pad82)") (class "Default")
      (node (ref "IC8") (pin "82") (pinfunction "PD13_82") (pintype "bidirectional"))
    )
    (net (code "178") (name "unconnected-(IC8B-PG2-Pad87)") (class "Default")
      (node (ref "IC8") (pin "87") (pinfunction "PG2_87") (pintype "bidirectional"))
    )
    (net (code "179") (name "unconnected-(IC8B-PG3-Pad88)") (class "Default")
      (node (ref "IC8") (pin "88") (pinfunction "PG3_88") (pintype "bidirectional"))
    )
    (net (code "180") (name "unconnected-(IC8B-PG6-Pad91)") (class "Default")
      (node (ref "IC8") (pin "91") (pinfunction "PG6_91") (pintype "bidirectional"))
    )
    (net (code "181") (name "unconnected-(IC8B-PG7-Pad92)") (class "Default")
      (node (ref "IC8") (pin "92") (pinfunction "PG7_92") (pintype "bidirectional"))
    )
    (net (code "182") (name "unconnected-(IC8C-PA8-Pad100)") (class "Default")
      (node (ref "IC8") (pin "100") (pinfunction "PA8_100") (pintype "bidirectional"))
    )
    (net (code "183") (name "unconnected-(IC8C-PB7-Pad137)") (class "Default")
      (node (ref "IC8") (pin "137") (pinfunction "PB7_137") (pintype "bidirectional"))
    )
    (net (code "184") (name "unconnected-(IC8C-PB8-Pad139)") (class "Default")
      (node (ref "IC8") (pin "139") (pinfunction "PB8_139") (pintype "bidirectional"))
    )
    (net (code "185") (name "unconnected-(IC8C-PB9-Pad140)") (class "Default")
      (node (ref "IC8") (pin "140") (pinfunction "PB9_140") (pintype "bidirectional"))
    )
    (net (code "186") (name "unconnected-(IC8C-PC7-Pad97)") (class "Default")
      (node (ref "IC8") (pin "97") (pinfunction "PC7_97") (pintype "bidirectional"))
    )
    (net (code "187") (name "unconnected-(IC8C-PC8-Pad98)") (class "Default")
      (node (ref "IC8") (pin "98") (pinfunction "PC8_98") (pintype "bidirectional"))
    )
    (net (code "188") (name "unconnected-(IC8C-PD5-Pad119)") (class "Default")
      (node (ref "IC8") (pin "119") (pinfunction "PD5_119") (pintype "bidirectional"))
    )
    (net (code "189") (name "unconnected-(IC8C-PD7-Pad123)") (class "Default")
      (node (ref "IC8") (pin "123") (pinfunction "PD7_123") (pintype "bidirectional"))
    )
    (net (code "190") (name "unconnected-(IC8C-PG11-Pad126)") (class "Default")
      (node (ref "IC8") (pin "126") (pinfunction "PG11_126") (pintype "bidirectional"))
    )
    (net (code "191") (name "unconnected-(IC8C-PG12-Pad127)") (class "Default")
      (node (ref "IC8") (pin "127") (pinfunction "PG12_127") (pintype "bidirectional"))
    )
    (net (code "192") (name "unconnected-(IC8C-PG13-Pad128)") (class "Default")
      (node (ref "IC8") (pin "128") (pinfunction "PG13_128") (pintype "bidirectional"))
    )
    (net (code "193") (name "unconnected-(X4G-1-Pad15)") (class "Default")
      (node (ref "X4") (pin "15") (pinfunction "1_15") (pintype "passive"))
    )
    (net (code "194") (name "unconnected-(X4S-1-Pad4)") (class "Default")
      (node (ref "X4") (pin "4") (pinfunction "1_4") (pintype "passive"))
    )
  )
)
